# nuc972_core.net
KiCad netlist of a schematic drawn in Altium Designer
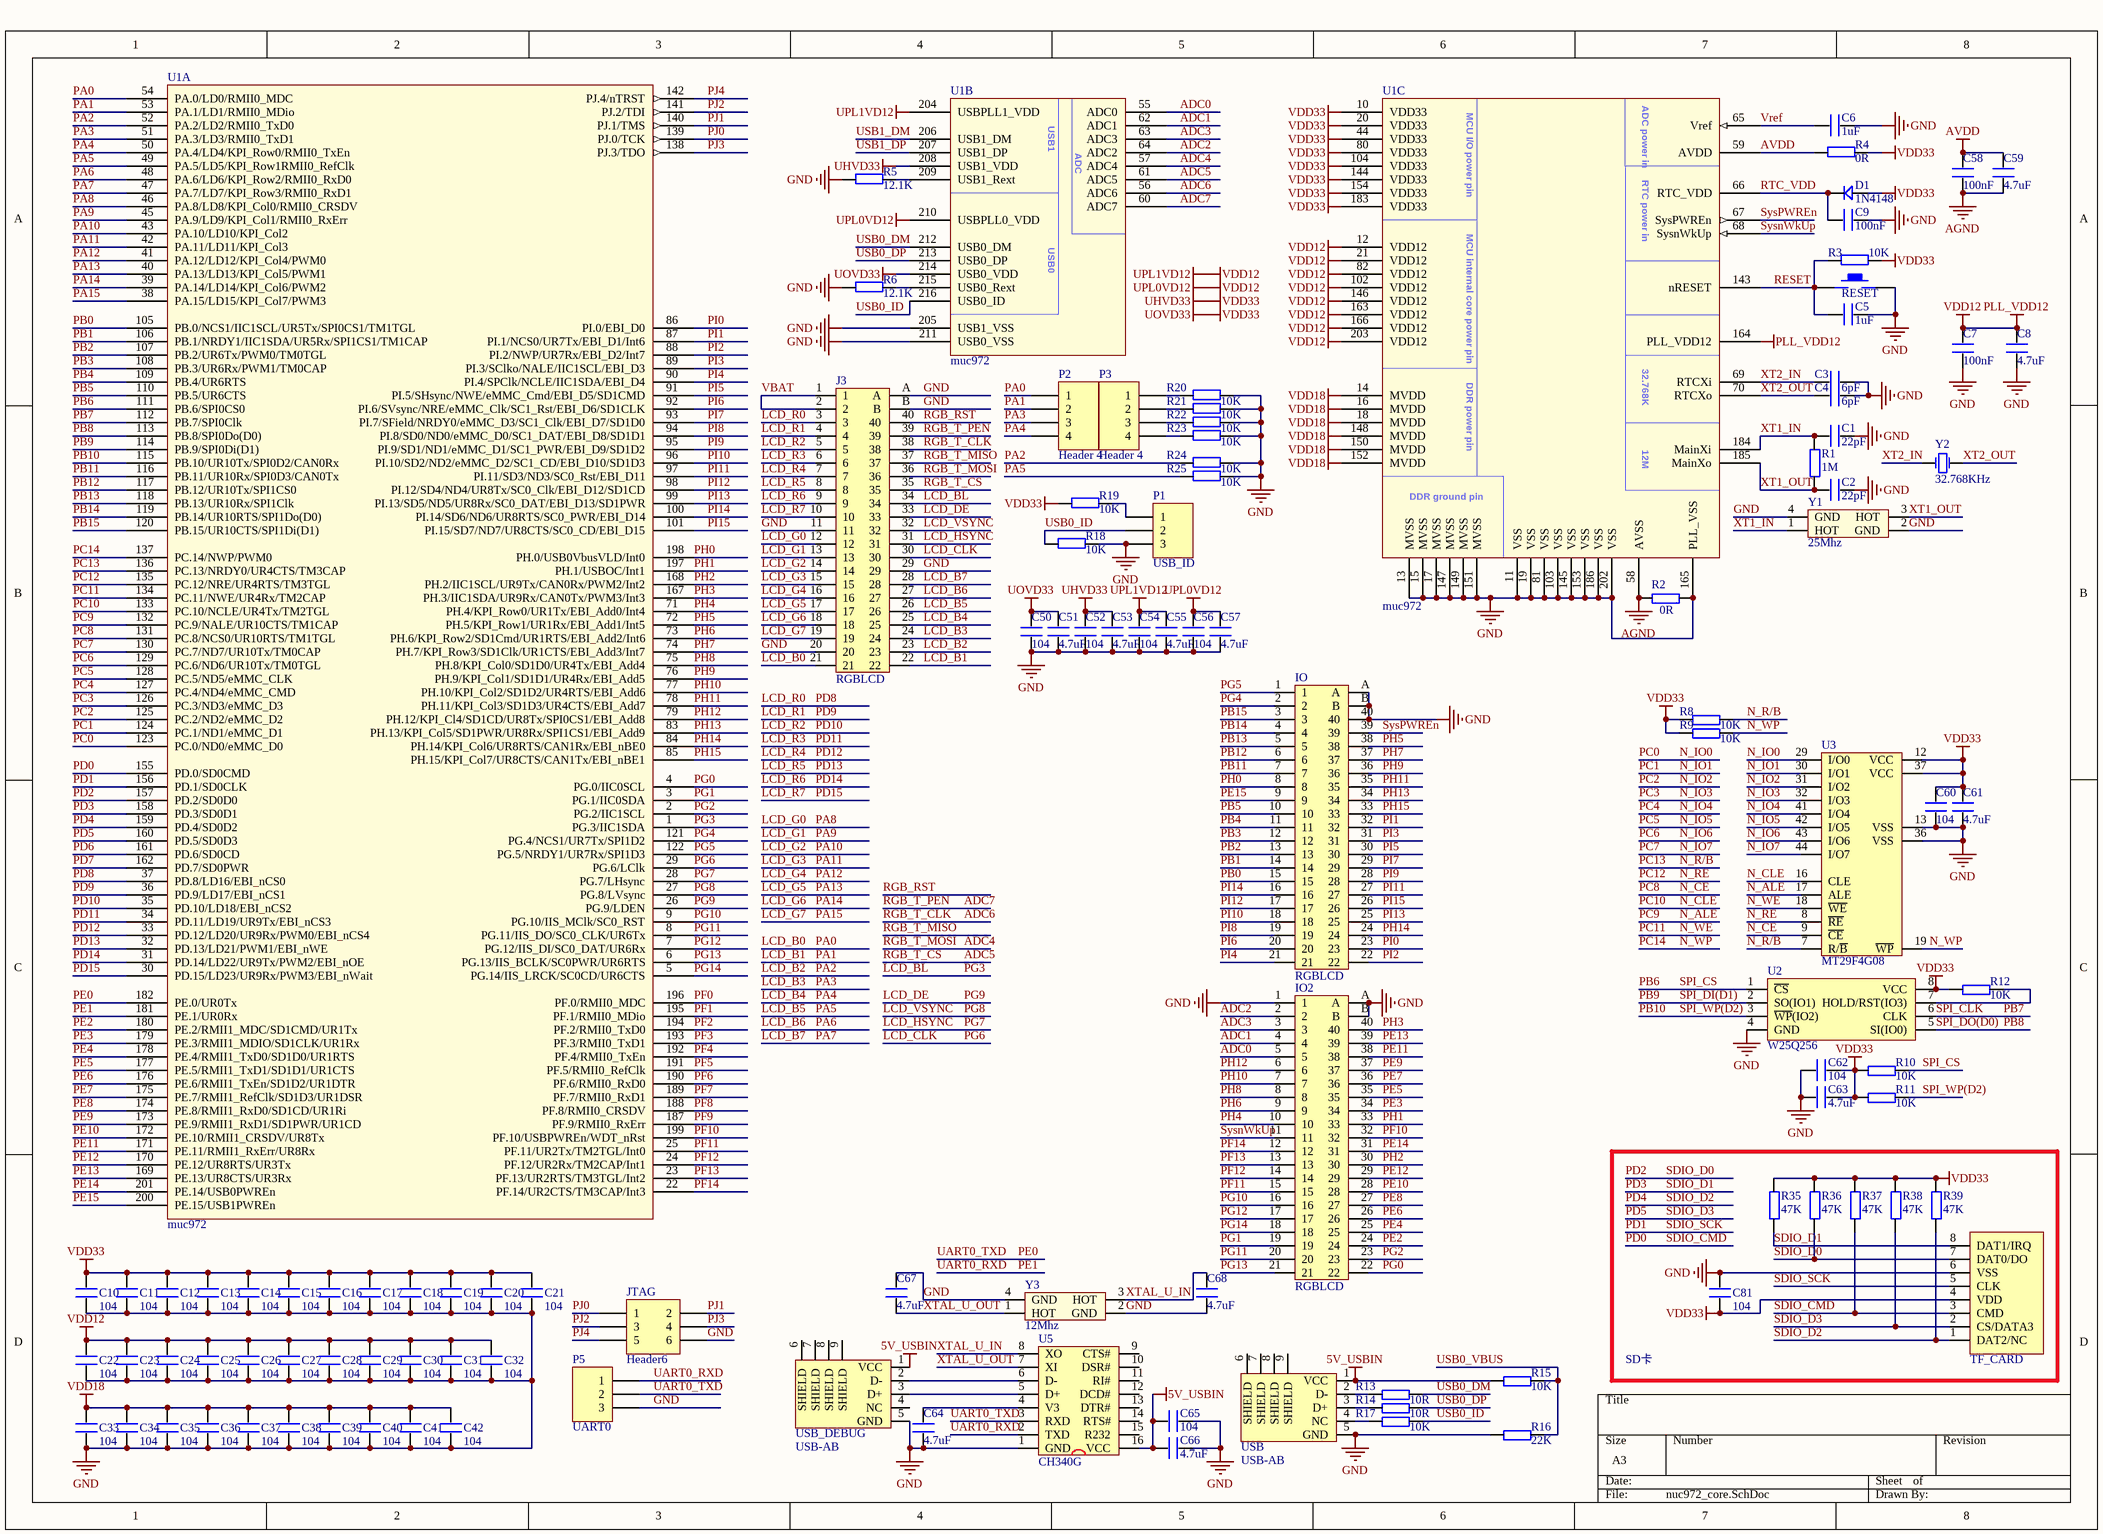
[diagram p0: nuc972_core.SchDoc]

(export (version "E")
  (design (tool "Eeschema 10.0.6"))
  (components
    (comp (ref "C1") (value "22pF") (footprint "C 0603_L") (libsource (lib "阿波罗STM32F4&F7底板封装库") (part "C")))
    (comp (ref "C2") (value "22pF") (footprint "C 0603_L") (libsource (lib "阿波罗STM32F4&F7底板封装库") (part "C")))
    (comp (ref "C3") (value "6pF") (footprint "C 0603_L") (libsource (lib "阿波罗STM32F4&F7底板封装库") (part "C")))
    (comp (ref "C4") (value "6pF") (footprint "C 0603_L") (libsource (lib "阿波罗STM32F4&F7底板封装库") (part "C")))
    (comp (ref "C5") (value "1uF") (footprint "C 0603_L") (libsource (lib "阿波罗STM32F4&F7底板封装库") (part "C")))
    (comp (ref "C6") (value "1uF") (footprint "C 0603_L") (libsource (lib "阿波罗STM32F4&F7底板封装库") (part "C")))
    (comp (ref "C7") (value "100nF") (footprint "C 0603_L") (libsource (lib "阿波罗STM32F4&F7底板封装库") (part "C")))
    (comp (ref "C8") (value "4.7uF") (footprint "C 0603_L") (libsource (lib "阿波罗STM32F4&F7底板封装库") (part "C")))
    (comp (ref "C9") (value "100nF") (footprint "C 0603_L") (libsource (lib "阿波罗STM32F4&F7底板封装库") (part "C")))
    (comp (ref "C10")
      (value "104")
      (footprint "C 0603_L")
      (libsource (lib "阿波罗STM32F4&F7&H7底板封装库") (part "C"))
    )
    (comp (ref "C11")
      (value "104")
      (footprint "C 0603_L")
      (libsource (lib "阿波罗STM32F4&F7&H7底板封装库") (part "C"))
    )
    (comp (ref "C12")
      (value "104")
      (footprint "C 0603_L")
      (libsource (lib "阿波罗STM32F4&F7&H7底板封装库") (part "C"))
    )
    (comp (ref "C13")
      (value "104")
      (footprint "C 0603_L")
      (libsource (lib "阿波罗STM32F4&F7&H7底板封装库") (part "C"))
    )
    (comp (ref "C14")
      (value "104")
      (footprint "C 0603_L")
      (libsource (lib "阿波罗STM32F4&F7&H7底板封装库") (part "C"))
    )
    (comp (ref "C15")
      (value "104")
      (footprint "C 0603_L")
      (libsource (lib "阿波罗STM32F4&F7&H7底板封装库") (part "C"))
    )
    (comp (ref "C16")
      (value "104")
      (footprint "C 0603_L")
      (libsource (lib "阿波罗STM32F4&F7&H7底板封装库") (part "C"))
    )
    (comp (ref "C17")
      (value "104")
      (footprint "C 0603_L")
      (libsource (lib "阿波罗STM32F4&F7&H7底板封装库") (part "C"))
    )
    (comp (ref "C18")
      (value "104")
      (footprint "C 0603_L")
      (libsource (lib "阿波罗STM32F4&F7&H7底板封装库") (part "C"))
    )
    (comp (ref "C19")
      (value "104")
      (footprint "C 0603_L")
      (libsource (lib "阿波罗STM32F4&F7&H7底板封装库") (part "C"))
    )
    (comp (ref "C20")
      (value "104")
      (footprint "C 0603_L")
      (libsource (lib "阿波罗STM32F4&F7&H7底板封装库") (part "C"))
    )
    (comp (ref "C21")
      (value "104")
      (footprint "C 0603_L")
      (libsource (lib "阿波罗STM32F4&F7&H7底板封装库") (part "C"))
    )
    (comp (ref "C22")
      (value "104")
      (footprint "C 0603_L")
      (libsource (lib "阿波罗STM32F4&F7&H7底板封装库") (part "C"))
    )
    (comp (ref "C23")
      (value "104")
      (footprint "C 0603_L")
      (libsource (lib "阿波罗STM32F4&F7&H7底板封装库") (part "C"))
    )
    (comp (ref "C24")
      (value "104")
      (footprint "C 0603_L")
      (libsource (lib "阿波罗STM32F4&F7&H7底板封装库") (part "C"))
    )
    (comp (ref "C25")
      (value "104")
      (footprint "C 0603_L")
      (libsource (lib "阿波罗STM32F4&F7&H7底板封装库") (part "C"))
    )
    (comp (ref "C26")
      (value "104")
      (footprint "C 0603_L")
      (libsource (lib "阿波罗STM32F4&F7&H7底板封装库") (part "C"))
    )
    (comp (ref "C27")
      (value "104")
      (footprint "C 0603_L")
      (libsource (lib "阿波罗STM32F4&F7&H7底板封装库") (part "C"))
    )
    (comp (ref "C28")
      (value "104")
      (footprint "C 0603_L")
      (libsource (lib "阿波罗STM32F4&F7&H7底板封装库") (part "C"))
    )
    (comp (ref "C29")
      (value "104")
      (footprint "C 0603_L")
      (libsource (lib "阿波罗STM32F4&F7&H7底板封装库") (part "C"))
    )
    (comp (ref "C30")
      (value "104")
      (footprint "C 0603_L")
      (libsource (lib "阿波罗STM32F4&F7&H7底板封装库") (part "C"))
    )
    (comp (ref "C31")
      (value "104")
      (footprint "C 0603_L")
      (libsource (lib "阿波罗STM32F4&F7&H7底板封装库") (part "C"))
    )
    (comp (ref "C32")
      (value "104")
      (footprint "C 0603_L")
      (libsource (lib "阿波罗STM32F4&F7&H7底板封装库") (part "C"))
    )
    (comp (ref "C33")
      (value "104")
      (footprint "C 0603_L")
      (libsource (lib "阿波罗STM32F4&F7&H7底板封装库") (part "C"))
    )
    (comp (ref "C34")
      (value "104")
      (footprint "C 0603_L")
      (libsource (lib "阿波罗STM32F4&F7&H7底板封装库") (part "C"))
    )
    (comp (ref "C35")
      (value "104")
      (footprint "C 0603_L")
      (libsource (lib "阿波罗STM32F4&F7&H7底板封装库") (part "C"))
    )
    (comp (ref "C36")
      (value "104")
      (footprint "C 0603_L")
      (libsource (lib "阿波罗STM32F4&F7&H7底板封装库") (part "C"))
    )
    (comp (ref "C37")
      (value "104")
      (footprint "C 0603_L")
      (libsource (lib "阿波罗STM32F4&F7&H7底板封装库") (part "C"))
    )
    (comp (ref "C38")
      (value "104")
      (footprint "C 0603_L")
      (libsource (lib "阿波罗STM32F4&F7&H7底板封装库") (part "C"))
    )
    (comp (ref "C39")
      (value "104")
      (footprint "C 0603_L")
      (libsource (lib "阿波罗STM32F4&F7&H7底板封装库") (part "C"))
    )
    (comp (ref "C40")
      (value "104")
      (footprint "C 0603_L")
      (libsource (lib "阿波罗STM32F4&F7&H7底板封装库") (part "C"))
    )
    (comp (ref "C41")
      (value "104")
      (footprint "C 0603_L")
      (libsource (lib "阿波罗STM32F4&F7&H7底板封装库") (part "C"))
    )
    (comp (ref "C42")
      (value "104")
      (footprint "C 0603_L")
      (libsource (lib "阿波罗STM32F4&F7&H7底板封装库") (part "C"))
    )
    (comp (ref "C50")
      (value "104")
      (footprint "C 0603_L")
      (libsource (lib "阿波罗STM32F4&F7&H7底板封装库") (part "C"))
    )
    (comp (ref "C51")
      (value "4.7uF")
      (footprint "C 0603_L")
      (libsource (lib "阿波罗STM32F4&F7&H7底板封装库") (part "C"))
    )
    (comp (ref "C52")
      (value "104")
      (footprint "C 0603_L")
      (libsource (lib "阿波罗STM32F4&F7&H7底板封装库") (part "C"))
    )
    (comp (ref "C53")
      (value "4.7uF")
      (footprint "C 0603_L")
      (libsource (lib "阿波罗STM32F4&F7&H7底板封装库") (part "C"))
    )
    (comp (ref "C54")
      (value "104")
      (footprint "C 0603_L")
      (libsource (lib "阿波罗STM32F4&F7&H7底板封装库") (part "C"))
    )
    (comp (ref "C55")
      (value "4.7uF")
      (footprint "C 0603_L")
      (libsource (lib "阿波罗STM32F4&F7&H7底板封装库") (part "C"))
    )
    (comp (ref "C56")
      (value "104")
      (footprint "C 0603_L")
      (libsource (lib "阿波罗STM32F4&F7&H7底板封装库") (part "C"))
    )
    (comp (ref "C57")
      (value "4.7uF")
      (footprint "C 0603_L")
      (libsource (lib "阿波罗STM32F4&F7&H7底板封装库") (part "C"))
    )
    (comp (ref "C58")
      (value "100nF")
      (footprint "C 0603_L")
      (libsource (lib "阿波罗STM32F4&F7底板封装库") (part "C"))
    )
    (comp (ref "C59")
      (value "4.7uF")
      (footprint "C 0603_L")
      (libsource (lib "阿波罗STM32F4&F7底板封装库") (part "C"))
    )
    (comp (ref "C60")
      (value "104")
      (footprint "C 0603_L")
      (libsource (lib "阿波罗STM32F4&F7&H7底板封装库") (part "C"))
    )
    (comp (ref "C61")
      (value "4.7uF")
      (footprint "C 0603_L")
      (libsource (lib "阿波罗STM32F4&F7&H7底板封装库") (part "C"))
    )
    (comp (ref "C62")
      (value "104")
      (footprint "C 0603_L")
      (libsource (lib "阿波罗STM32F4&F7&H7底板封装库") (part "C"))
    )
    (comp (ref "C63")
      (value "4.7uF")
      (footprint "C 0603_L")
      (libsource (lib "阿波罗STM32F4&F7&H7底板封装库") (part "C"))
    )
    (comp (ref "C64")
      (value "4.7uF")
      (footprint "C 0603_L")
      (libsource (lib "阿波罗STM32F4&F7&H7底板封装库") (part "C"))
    )
    (comp (ref "C65")
      (value "104")
      (footprint "C 0603_L")
      (libsource (lib "阿波罗STM32F4&F7&H7底板封装库") (part "C"))
    )
    (comp (ref "C66")
      (value "4.7uF")
      (footprint "C 0603_L")
      (libsource (lib "阿波罗STM32F4&F7&H7底板封装库") (part "C"))
    )
    (comp (ref "C67")
      (value "4.7uF")
      (footprint "C 0603_L")
      (libsource (lib "阿波罗STM32F4&F7&H7底板封装库") (part "C"))
    )
    (comp (ref "C68")
      (value "4.7uF")
      (footprint "C 0603_L")
      (libsource (lib "阿波罗STM32F4&F7&H7底板封装库") (part "C"))
    )
    (comp (ref "C81")
      (value "104")
      (footprint "C 0603_L")
      (libsource (lib "阿波罗STM32F4&F7&H7底板封装库") (part "C"))
    )
    (comp (ref "D1")
      (value "1N4148")
      (footprint "MINI_MELF (LL34)")
      (libsource (lib "阿波罗STM32F4&F7&H7底板封装库") (part "D"))
    )
    (comp (ref "IO")
      (value "RGBLCD")
      (footprint "FPC-TOP40")
      (description "FPC-40P-0.5mm")
      (libsource (lib "STM32F429核心板封装库") (part "FPC-40"))
    )
    (comp (ref "IO2")
      (value "RGBLCD")
      (footprint "FPC-TOP40")
      (description "FPC-40P-0.5mm")
      (libsource (lib "STM32F429核心板封装库") (part "FPC-40"))
    )
    (comp (ref "J3")
      (value "RGBLCD")
      (footprint "FPC-TOP40")
      (description "FPC-40P-0.5mm")
      (libsource (lib "STM32F429核心板封装库") (part "FPC-40"))
    )
    (comp (ref "JTAG")
      (value "Header6")
      (footprint "HDR2.54-LI-6P")
      (description "Header, 3-Pin, Dual row")
      (fields (field (name "PUBLISHER") "Altium Limited"))
      (libsource (lib "阿波罗STM32F4&F7底板封装库") (part "Header 3X2"))
    )
    (comp (ref "P1")
      (value "USB_ID")
      (footprint "HDR2.54-LI-3P")
      (description "Header, 3-Pin")
      (fields (field (name "PUBLISHER") "Altium Limited"))
      (libsource (lib "") (part "Header 3_1"))
    )
    (comp (ref "P2")
      (value "Header 4")
      (footprint "HDR2.54-LI-4P")
      (description "Header, 4-Pin")
      (fields (field (name "PUBLISHER") "Altium Limited"))
      (libsource (lib "阿波罗STM32F4&F7底板封装库") (part "Header 4"))
    )
    (comp (ref "P3")
      (value "Header 4")
      (footprint "HDR2.54-LI-4P")
      (description "Header, 4-Pin")
      (fields (field (name "PUBLISHER") "Altium Limited"))
      (libsource (lib "") (part "Header 4_1"))
    )
    (comp (ref "P5")
      (value "UART0")
      (footprint "HDR2.54-LI-3P")
      (description "Header, 3-Pin")
      (fields (field (name "PUBLISHER") "Altium Limited"))
      (libsource (lib "STM32H743核心板封装库") (part "Header 3"))
    )
    (comp (ref "R1") (value "1M") (footprint "R 0603_L") (libsource (lib "阿波罗STM32F4&F7底板封装库") (part "R")))
    (comp (ref "R2") (value "0R") (footprint "R 0603_L") (libsource (lib "阿波罗STM32F4&F7底板封装库") (part "R")))
    (comp (ref "R3") (value "10K") (footprint "R 0603_L") (libsource (lib "阿波罗STM32F4&F7底板封装库") (part "R")))
    (comp (ref "R4") (value "0R") (footprint "R 0603_L") (libsource (lib "阿波罗STM32F4&F7底板封装库") (part "R")))
    (comp (ref "R5") (value "12.1K") (footprint "R 0603_L") (libsource (lib "阿波罗STM32F4&F7底板封装库") (part "R")))
    (comp (ref "R6") (value "12.1K") (footprint "R 0603_L") (libsource (lib "阿波罗STM32F4&F7底板封装库") (part "R")))
    (comp (ref "R8") (value "10K") (footprint "R 0603_L") (libsource (lib "阿波罗STM32F4&F7底板封装库") (part "R")))
    (comp (ref "R9") (value "10K") (footprint "R 0603_L") (libsource (lib "阿波罗STM32F4&F7底板封装库") (part "R")))
    (comp (ref "R10") (value "10K") (footprint "R 0603_L") (libsource (lib "阿波罗STM32F4&F7底板封装库") (part "R")))
    (comp (ref "R11") (value "10K") (footprint "R 0603_L") (libsource (lib "阿波罗STM32F4&F7底板封装库") (part "R")))
    (comp (ref "R12") (value "10K") (footprint "R 0603_L") (libsource (lib "阿波罗STM32F4&F7底板封装库") (part "R")))
    (comp (ref "R13") (value "10R") (footprint "R 0603_L") (libsource (lib "阿波罗STM32F4&F7底板封装库") (part "R")))
    (comp (ref "R14") (value "10R") (footprint "R 0603_L") (libsource (lib "阿波罗STM32F4&F7底板封装库") (part "R")))
    (comp (ref "R15") (value "10K") (footprint "R 0603_L") (libsource (lib "阿波罗STM32F4&F7底板封装库") (part "R")))
    (comp (ref "R16") (value "22K") (footprint "R 0603_L") (libsource (lib "阿波罗STM32F4&F7底板封装库") (part "R")))
    (comp (ref "R17") (value "10K") (footprint "R 0603_L") (libsource (lib "阿波罗STM32F4&F7底板封装库") (part "R")))
    (comp (ref "R18") (value "10K") (footprint "R 0603_L") (libsource (lib "阿波罗STM32F4&F7底板封装库") (part "R")))
    (comp (ref "R19") (value "10K") (footprint "R 0603_L") (libsource (lib "阿波罗STM32F4&F7底板封装库") (part "R")))
    (comp (ref "R20") (value "10K") (footprint "R 0603_L") (libsource (lib "阿波罗STM32F4&F7底板封装库") (part "R")))
    (comp (ref "R21") (value "10K") (footprint "R 0603_L") (libsource (lib "阿波罗STM32F4&F7底板封装库") (part "R")))
    (comp (ref "R22") (value "10K") (footprint "R 0603_L") (libsource (lib "阿波罗STM32F4&F7底板封装库") (part "R")))
    (comp (ref "R23") (value "10K") (footprint "R 0603_L") (libsource (lib "阿波罗STM32F4&F7底板封装库") (part "R")))
    (comp (ref "R24") (value "10K") (footprint "R 0603_L") (libsource (lib "阿波罗STM32F4&F7底板封装库") (part "R")))
    (comp (ref "R25") (value "10K") (footprint "R 0603_L") (libsource (lib "阿波罗STM32F4&F7底板封装库") (part "R")))
    (comp (ref "R35") (value "47K") (footprint "R 0603_L") (libsource (lib "阿波罗STM32F4&F7底板封装库") (part "R")))
    (comp (ref "R36") (value "47K") (footprint "R 0603_L") (libsource (lib "阿波罗STM32F4&F7底板封装库") (part "R")))
    (comp (ref "R37") (value "47K") (footprint "R 0603_L") (libsource (lib "阿波罗STM32F4&F7底板封装库") (part "R")))
    (comp (ref "R38") (value "47K") (footprint "R 0603_L") (libsource (lib "阿波罗STM32F4&F7底板封装库") (part "R")))
    (comp (ref "R39") (value "47K") (footprint "R 0603_L") (libsource (lib "阿波罗STM32F4&F7底板封装库") (part "R")))
    (comp (ref "RESET")
      (value "KEY_M")
      (footprint "TSW DIP-6*6*5")
      (libsource (lib "阿波罗STM32F4&F7&H7底板封装库") (part "KEY_M"))
    )
    (comp (ref "TF_CARD")
      (value "SD-MICRO-TF")
      (footprint "SD-MICRO-TF")
      (description "SD,MICRO,TF")
      (libsource (lib "Pandora_STM32L4_Board_V2.4") (part "SD-MICRO-TF"))
    )
    (comp (ref "U1") (value "muc972") (footprint "LQFP_216") (libsource (lib "nuc972lib") (part "LQFP_216")))
    (comp (ref "U2")
      (value "W25Q256")
      (footprint "SOP8W_N")
      (description "W25Q128")
      (libsource (lib "STM32H743核心板封装库") (part "W25Q128"))
    )
    (comp (ref "U3")
      (value "MT29F4G08")
      (footprint "TSOP48")
      (description "256MB NAND FLASH")
      (libsource (lib "STM32H743核心板封装库") (part "K9F2G08U0C"))
    )
    (comp (ref "U5")
      (value "CH340G")
      (footprint "SOP16_N")
      (description "USB2UART")
      (libsource (lib "阿波罗STM32F4&F7底板封装库") (part "CH340G"))
    )
    (comp (ref "USB")
      (value "USB-AB")
      (footprint "USB-MICRO_B")
      (description "MicroUSB")
      (libsource (lib "STM32H743核心板封装库") (part "USB-AB"))
    )
    (comp (ref "USB_DEBUG")
      (value "USB-AB")
      (footprint "USB-MICRO_B")
      (description "MicroUSB")
      (libsource (lib "STM32H743核心板封装库") (part "USB-AB"))
    )
    (comp (ref "Y1")
      (value "25Mhz")
      (footprint "OSC 3225-4P")
      (description "3225贴片无源晶振")
      (libsource (lib "STM32H743核心板封装库") (part "XTAL_3225"))
    )
    (comp (ref "Y2")
      (value "32.768KHz")
      (footprint "OSC 3215-2P")
      (description "普通晶振")
      (fields (field (name "PUBLISHER") "Altium Limited"))
      (libsource (lib "STM32H743核心板封装库") (part "XTAL"))
    )
    (comp (ref "Y3")
      (value "12Mhz")
      (footprint "OSC 3225-4P")
      (description "3225贴片无源晶振")
      (libsource (lib "STM32H743核心板封装库") (part "XTAL_3225"))
    )
  )
  (nets
    (net (code "1") (name "/ADC0") (class "Default")
      (node (ref "IO2") (pin "5") (pinfunction "5_5") (pintype "passive"))
      (node (ref "U1") (pin "55") (pinfunction "ADC0_55") (pintype "passive"))
    )
    (net (code "2") (name "/ADC1") (class "Default")
      (node (ref "IO2") (pin "4") (pinfunction "4_4") (pintype "passive"))
      (node (ref "U1") (pin "62") (pinfunction "ADC1_62") (pintype "passive"))
    )
    (net (code "3") (name "/ADC2") (class "Default")
      (node (ref "IO2") (pin "2") (pinfunction "2_2") (pintype "passive"))
      (node (ref "U1") (pin "64") (pinfunction "ADC2_64") (pintype "passive"))
    )
    (net (code "4") (name "/ADC3") (class "Default")
      (node (ref "IO2") (pin "3") (pinfunction "3_3") (pintype "passive"))
      (node (ref "U1") (pin "63") (pinfunction "ADC3_63") (pintype "passive"))
    )
    (net (code "5") (name "/ADC4") (class "Default")
      (node (ref "J3") (pin "36") (pinfunction "36_36") (pintype "passive"))
      (node (ref "U1") (pin "57") (pinfunction "ADC4_57") (pintype "passive"))
    )
    (net (code "6") (name "/ADC5") (class "Default")
      (node (ref "J3") (pin "35") (pinfunction "35_35") (pintype "passive"))
      (node (ref "U1") (pin "61") (pinfunction "ADC5_61") (pintype "passive"))
    )
    (net (code "7") (name "/ADC6") (class "Default")
      (node (ref "J3") (pin "38") (pinfunction "38_38") (pintype "passive"))
      (node (ref "U1") (pin "56") (pinfunction "ADC6_56") (pintype "passive"))
    )
    (net (code "8") (name "/ADC7") (class "Default")
      (node (ref "J3") (pin "39") (pinfunction "39_39") (pintype "passive"))
      (node (ref "U1") (pin "60") (pinfunction "ADC7_60") (pintype "passive"))
    )
    (net (code "9") (name "/LCD_B0") (class "Default")
      (node (ref "J3") (pin "21") (pinfunction "21_21") (pintype "passive"))
      (node (ref "P2") (pin "1") (pinfunction "1_1") (pintype "passive"))
      (node (ref "U1") (pin "54") (pinfunction "PA.0/LD0/RMII0_MDC_54") (pintype "passive"))
    )
    (net (code "10") (name "/LCD_B1") (class "Default")
      (node (ref "J3") (pin "22") (pinfunction "22_22") (pintype "passive"))
      (node (ref "P2") (pin "2") (pinfunction "2_2") (pintype "passive"))
      (node (ref "U1") (pin "53") (pinfunction "PA.1/LD1/RMII0_MDio_53") (pintype "passive"))
    )
    (net (code "11") (name "/LCD_B2") (class "Default")
      (node (ref "J3") (pin "23") (pinfunction "23_23") (pintype "passive"))
      (node (ref "R24") (pin "2") (pintype "passive"))
      (node (ref "U1") (pin "52") (pinfunction "PA.2/LD2/RMII0_TxD0_52") (pintype "passive"))
    )
    (net (code "12") (name "/LCD_B3") (class "Default")
      (node (ref "J3") (pin "24") (pinfunction "24_24") (pintype "passive"))
      (node (ref "P2") (pin "3") (pinfunction "3_3") (pintype "passive"))
      (node (ref "U1") (pin "51") (pinfunction "PA.3/LD3/RMII0_TxD1_51") (pintype "passive"))
    )
    (net (code "13") (name "/LCD_B4") (class "Default")
      (node (ref "J3") (pin "25") (pinfunction "25_25") (pintype "passive"))
      (node (ref "P2") (pin "4") (pinfunction "4_4") (pintype "passive"))
      (node (ref "U1") (pin "50") (pinfunction "PA.4/LD4/KPI_Row0/RMII0_TxEn_50") (pintype "passive"))
    )
    (net (code "14") (name "/LCD_B5") (class "Default")
      (node (ref "J3") (pin "26") (pinfunction "26_26") (pintype "passive"))
      (node (ref "R25") (pin "2") (pintype "passive"))
      (node (ref "U1") (pin "49") (pinfunction "PA.5/LD5/KPI_Row1RMII0_RefClk_49") (pintype "passive"))
    )
    (net (code "15") (name "/LCD_B6") (class "Default")
      (node (ref "J3") (pin "27") (pinfunction "27_27") (pintype "passive"))
      (node (ref "U1") (pin "48") (pinfunction "PA.6/LD6/KPI_Row2/RMII0_RxD0_48") (pintype "passive"))
    )
    (net (code "16") (name "/LCD_B7") (class "Default")
      (node (ref "J3") (pin "28") (pinfunction "28_28") (pintype "passive"))
      (node (ref "U1") (pin "47") (pinfunction "PA.7/LD7/KPI_Row3/RMII0_RxD1_47") (pintype "passive"))
    )
    (net (code "17") (name "/LCD_BL") (class "Default")
      (node (ref "J3") (pin "34") (pinfunction "34_34") (pintype "passive"))
      (node (ref "U1") (pin "1") (pinfunction "PG.3/IIC1SDA_1") (pintype "passive"))
    )
    (net (code "18") (name "/LCD_CLK") (class "Default")
      (node (ref "J3") (pin "30") (pinfunction "30_30") (pintype "passive"))
      (node (ref "U1") (pin "29") (pinfunction "PG.6/LClk_29") (pintype "passive"))
    )
    (net (code "19") (name "/LCD_DE") (class "Default")
      (node (ref "J3") (pin "33") (pinfunction "33_33") (pintype "passive"))
      (node (ref "U1") (pin "26") (pinfunction "PG.9/LDEN_26") (pintype "passive"))
    )
    (net (code "20") (name "/LCD_G0") (class "Default")
      (node (ref "J3") (pin "12") (pinfunction "12_12") (pintype "passive"))
      (node (ref "U1") (pin "46") (pinfunction "PA.8/LD8/KPI_Col0/RMII0_CRSDV_46") (pintype "passive"))
    )
    (net (code "21") (name "/LCD_G1") (class "Default")
      (node (ref "J3") (pin "13") (pinfunction "13_13") (pintype "passive"))
      (node (ref "U1") (pin "45") (pinfunction "PA.9/LD9/KPI_Col1/RMII0_RxErr_45") (pintype "passive"))
    )
    (net (code "22") (name "/LCD_G2") (class "Default")
      (node (ref "J3") (pin "14") (pinfunction "14_14") (pintype "passive"))
      (node (ref "U1") (pin "43") (pinfunction "PA.10/LD10/KPI_Col2_43") (pintype "passive"))
    )
    (net (code "23") (name "/LCD_G3") (class "Default")
      (node (ref "J3") (pin "15") (pinfunction "15_15") (pintype "passive"))
      (node (ref "U1") (pin "42") (pinfunction "PA.11/LD11/KPI_Col3_42") (pintype "passive"))
    )
    (net (code "24") (name "/LCD_G4") (class "Default")
      (node (ref "J3") (pin "16") (pinfunction "16_16") (pintype "passive"))
      (node (ref "U1") (pin "41") (pinfunction "PA.12/LD12/KPI_Col4/PWM0_41") (pintype "passive"))
    )
    (net (code "25") (name "/LCD_G5") (class "Default")
      (node (ref "J3") (pin "17") (pinfunction "17_17") (pintype "passive"))
      (node (ref "U1") (pin "40") (pinfunction "PA.13/LD13/KPI_Col5/PWM1_40") (pintype "passive"))
    )
    (net (code "26") (name "/LCD_G6") (class "Default")
      (node (ref "J3") (pin "18") (pinfunction "18_18") (pintype "passive"))
      (node (ref "U1") (pin "39") (pinfunction "PA.14/LD14/KPI_Col6/PWM2_39") (pintype "passive"))
    )
    (net (code "27") (name "/LCD_G7") (class "Default")
      (node (ref "J3") (pin "19") (pinfunction "19_19") (pintype "passive"))
      (node (ref "U1") (pin "38") (pinfunction "PA.15/LD15/KPI_Col7/PWM3_38") (pintype "passive"))
    )
    (net (code "28") (name "/LCD_HSYNC") (class "Default")
      (node (ref "J3") (pin "31") (pinfunction "31_31") (pintype "passive"))
      (node (ref "U1") (pin "28") (pinfunction "PG.7/LHsync_28") (pintype "passive"))
    )
    (net (code "29") (name "/LCD_R0") (class "Default")
      (node (ref "J3") (pin "3") (pinfunction "3_3") (pintype "passive"))
      (node (ref "U1") (pin "37") (pinfunction "PD.8/LD16/EBI_nCS0_37") (pintype "passive"))
    )
    (net (code "30") (name "/LCD_R1") (class "Default")
      (node (ref "J3") (pin "4") (pinfunction "4_4") (pintype "passive"))
      (node (ref "U1") (pin "36") (pinfunction "PD.9/LD17/EBI_nCS1_36") (pintype "passive"))
    )
    (net (code "31") (name "/LCD_R2") (class "Default")
      (node (ref "J3") (pin "5") (pinfunction "5_5") (pintype "passive"))
      (node (ref "U1") (pin "35") (pinfunction "PD.10/LD18/EBI_nCS2_35") (pintype "passive"))
    )
    (net (code "32") (name "/LCD_R3") (class "Default")
      (node (ref "J3") (pin "6") (pinfunction "6_6") (pintype "passive"))
      (node (ref "U1") (pin "34") (pinfunction "PD.11/LD19/UR9Tx/EBI_nCS3_34") (pintype "passive"))
    )
    (net (code "33") (name "/LCD_R4") (class "Default")
      (node (ref "J3") (pin "7") (pinfunction "7_7") (pintype "passive"))
      (node (ref "U1") (pin "33") (pinfunction "PD.12/LD20/UR9Rx/PWM0/EBI_nCS4_33") (pintype "passive"))
    )
    (net (code "34") (name "/LCD_R5") (class "Default")
      (node (ref "J3") (pin "8") (pinfunction "8_8") (pintype "passive"))
      (node (ref "U1") (pin "32") (pinfunction "PD.13/LD21/PWM1/EBI_nWE_32") (pintype "passive"))
    )
    (net (code "35") (name "/LCD_R6") (class "Default")
      (node (ref "J3") (pin "9") (pinfunction "9_9") (pintype "passive"))
      (node (ref "U1") (pin "31") (pinfunction "PD.14/LD22/UR9Tx/PWM2/EBI_nOE_31") (pintype "passive"))
    )
    (net (code "36") (name "/LCD_R7") (class "Default")
      (node (ref "J3") (pin "10") (pinfunction "10_10") (pintype "passive"))
      (node (ref "U1") (pin "30") (pinfunction "PD.15/LD23/UR9Rx/PWM3/EBI_nWait_30") (pintype "passive"))
    )
    (net (code "37") (name "/LCD_VSYNC") (class "Default")
      (node (ref "J3") (pin "32") (pinfunction "32_32") (pintype "passive"))
      (node (ref "U1") (pin "27") (pinfunction "PG.8/LVsync_27") (pintype "passive"))
    )
    (net (code "38") (name "/N_ALE") (class "Default")
      (node (ref "U1") (pin "132") (pinfunction "PC.9/NALE/UR10CTS/TM1CAP_132") (pintype "passive"))
      (node (ref "U3") (pin "17") (pinfunction "ALE_17") (pintype "passive"))
    )
    (net (code "39") (name "/N_CE") (class "Default")
      (node (ref "U1") (pin "131") (pinfunction "PC.8/NCS0/UR10RTS/TM1TGL_131") (pintype "passive"))
      (node (ref "U3") (pin "9") (pinfunction "~{CE}_9") (pintype "passive"))
    )
    (net (code "40") (name "/N_CLE") (class "Default")
      (node (ref "U1") (pin "133") (pinfunction "PC.10/NCLE/UR4Tx/TM2TGL_133") (pintype "passive"))
      (node (ref "U3") (pin "16") (pinfunction "CLE_16") (pintype "passive"))
    )
    (net (code "41") (name "/N_IO0") (class "Default")
      (node (ref "U1") (pin "123") (pinfunction "PC.0/ND0/eMMC_D0_123") (pintype "passive"))
      (node (ref "U3") (pin "29") (pinfunction "I/O0_29") (pintype "passive"))
    )
    (net (code "42") (name "/N_IO1") (class "Default")
      (node (ref "U1") (pin "124") (pinfunction "PC.1/ND1/eMMC_D1_124") (pintype "passive"))
      (node (ref "U3") (pin "30") (pinfunction "I/O1_30") (pintype "passive"))
    )
    (net (code "43") (name "/N_IO2") (class "Default")
      (node (ref "U1") (pin "125") (pinfunction "PC.2/ND2/eMMC_D2_125") (pintype "passive"))
      (node (ref "U3") (pin "31") (pinfunction "I/O2_31") (pintype "passive"))
    )
    (net (code "44") (name "/N_IO3") (class "Default")
      (node (ref "U1") (pin "126") (pinfunction "PC.3/ND3/eMMC_D3_126") (pintype "passive"))
      (node (ref "U3") (pin "32") (pinfunction "I/O3_32") (pintype "passive"))
    )
    (net (code "45") (name "/N_IO4") (class "Default")
      (node (ref "U1") (pin "127") (pinfunction "PC.4/ND4/eMMC_CMD_127") (pintype "passive"))
      (node (ref "U3") (pin "41") (pinfunction "I/O4_41") (pintype "passive"))
    )
    (net (code "46") (name "/N_IO5") (class "Default")
      (node (ref "U1") (pin "128") (pinfunction "PC.5/ND5/eMMC_CLK_128") (pintype "passive"))
      (node (ref "U3") (pin "42") (pinfunction "I/O5_42") (pintype "passive"))
    )
    (net (code "47") (name "/N_IO6") (class "Default")
      (node (ref "U1") (pin "129") (pinfunction "PC.6/ND6/UR10Tx/TM0TGL_129") (pintype "passive"))
      (node (ref "U3") (pin "43") (pinfunction "I/O6_43") (pintype "passive"))
    )
    (net (code "48") (name "/N_IO7") (class "Default")
      (node (ref "U1") (pin "130") (pinfunction "PC.7/ND7/UR10Tx/TM0CAP_130") (pintype "passive"))
      (node (ref "U3") (pin "44") (pinfunction "I/O7_44") (pintype "passive"))
    )
    (net (code "49") (name "/N_RE") (class "Default")
      (node (ref "U1") (pin "135") (pinfunction "PC.12/NRE/UR4RTS/TM3TGL_135") (pintype "passive"))
      (node (ref "U3") (pin "8") (pinfunction "~{RE}_8") (pintype "passive"))
    )
    (net (code "50") (name "/N_R{slash}B") (class "Default")
      (node (ref "R8") (pin "2") (pintype "passive"))
      (node (ref "U1") (pin "136") (pinfunction "PC.13/NRDY0/UR4CTS/TM3CAP_136") (pintype "passive"))
      (node (ref "U3") (pin "7") (pinfunction "R/~{B}_7") (pintype "passive"))
    )
    (net (code "51") (name "/N_WE") (class "Default")
      (node (ref "U1") (pin "134") (pinfunction "PC.11/NWE/UR4Rx/TM2CAP_134") (pintype "passive"))
      (node (ref "U3") (pin "18") (pinfunction "~{WE}_18") (pintype "passive"))
    )
    (net (code "52") (name "/N_WP") (class "Default")
      (node (ref "R9") (pin "2") (pintype "passive"))
      (node (ref "U1") (pin "137") (pinfunction "PC.14/NWP/PWM0_137") (pintype "passive"))
      (node (ref "U3") (pin "19") (pinfunction "~{WP}_19") (pintype "passive"))
    )
    (net (code "53") (name "/PB0") (class "Default")
      (node (ref "IO") (pin "15") (pinfunction "15_15") (pintype "passive"))
      (node (ref "U1") (pin "105") (pinfunction "PB.0/NCS1/IIC1SCL/UR5Tx/SPI0CS1/TM1TGL_105") (pintype "passive"))
    )
    (net (code "54") (name "/PB1") (class "Default")
      (node (ref "IO") (pin "14") (pinfunction "14_14") (pintype "passive"))
      (node (ref "U1") (pin "106") (pinfunction "PB.1/NRDY1/IIC1SDA/UR5Rx/SPI1CS1/TM1CAP_106") (pintype "passive"))
    )
    (net (code "55") (name "/PB2") (class "Default")
      (node (ref "IO") (pin "13") (pinfunction "13_13") (pintype "passive"))
      (node (ref "U1") (pin "107") (pinfunction "PB.2/UR6Tx/PWM0/TM0TGL_107") (pintype "passive"))
    )
    (net (code "56") (name "/PB3") (class "Default")
      (node (ref "IO") (pin "12") (pinfunction "12_12") (pintype "passive"))
      (node (ref "U1") (pin "108") (pinfunction "PB.3/UR6Rx/PWM1/TM0CAP_108") (pintype "passive"))
    )
    (net (code "57") (name "/PB4") (class "Default")
      (node (ref "IO") (pin "11") (pinfunction "11_11") (pintype "passive"))
      (node (ref "U1") (pin "109") (pinfunction "PB.4/UR6RTS_109") (pintype "passive"))
    )
    (net (code "58") (name "/PB5") (class "Default")
      (node (ref "IO") (pin "10") (pinfunction "10_10") (pintype "passive"))
      (node (ref "U1") (pin "110") (pinfunction "PB.5/UR6CTS_110") (pintype "passive"))
    )
    (net (code "59") (name "/PB6") (class "Default")
      (node (ref "R10") (pin "2") (pintype "passive"))
      (node (ref "U1") (pin "111") (pinfunction "PB.6/SPI0CS0_111") (pintype "passive"))
      (node (ref "U2") (pin "1") (pinfunction "~{CS}_1") (pintype "passive"))
    )
    (net (code "60") (name "/PB7") (class "Default")
      (node (ref "U1") (pin "112") (pinfunction "PB.7/SPI0Clk_112") (pintype "passive"))
      (node (ref "U2") (pin "6") (pinfunction "CLK_6") (pintype "passive"))
    )
    (net (code "61") (name "/PB8") (class "Default")
      (node (ref "U1") (pin "113") (pinfunction "PB.8/SPI0Do(D0)_113") (pintype "passive"))
      (node (ref "U2") (pin "5") (pinfunction "SI(IO0)_5") (pintype "power_in"))
    )
    (net (code "62") (name "/PB9") (class "Default")
      (node (ref "U1") (pin "114") (pinfunction "PB.9/SPI0Di(D1)_114") (pintype "passive"))
      (node (ref "U2") (pin "2") (pinfunction "SO(IO1)_2") (pintype "passive"))
    )
    (net (code "63") (name "/PB10") (class "Default")
      (node (ref "R11") (pin "2") (pintype "passive"))
      (node (ref "U1") (pin "115") (pinfunction "PB.10/UR10Tx/SPI0D2/CAN0Rx_115") (pintype "passive"))
      (node (ref "U2") (pin "3") (pinfunction "~{WP}(IO2)_3") (pintype "passive"))
    )
    (net (code "64") (name "/PB11") (class "Default")
      (node (ref "IO") (pin "7") (pinfunction "7_7") (pintype "passive"))
      (node (ref "U1") (pin "116") (pinfunction "PB.11/UR10Rx/SPI0D3/CAN0Tx_116") (pintype "passive"))
    )
    (net (code "65") (name "/PB12") (class "Default")
      (node (ref "IO") (pin "6") (pinfunction "6_6") (pintype "passive"))
      (node (ref "U1") (pin "117") (pinfunction "PB.12/UR10Tx/SPI1CS0_117") (pintype "passive"))
    )
    (net (code "66") (name "/PB13") (class "Default")
      (node (ref "IO") (pin "5") (pinfunction "5_5") (pintype "passive"))
      (node (ref "U1") (pin "118") (pinfunction "PB.13/UR10Rx/SPI1Clk_118") (pintype "passive"))
    )
    (net (code "67") (name "/PB14") (class "Default")
      (node (ref "IO") (pin "4") (pinfunction "4_4") (pintype "passive"))
      (node (ref "U1") (pin "119") (pinfunction "PB.14/UR10RTS/SPI1Do(D0)_119") (pintype "passive"))
    )
    (net (code "68") (name "/PB15") (class "Default")
      (node (ref "IO") (pin "3") (pinfunction "3_3") (pintype "passive"))
      (node (ref "U1") (pin "120") (pinfunction "PB.15/UR10CTS/SPI1Di(D1)_120") (pintype "passive"))
    )
    (net (code "69") (name "/PD0") (class "Default")
      (node (ref "R37") (pin "1") (pintype "passive"))
      (node (ref "TF_CARD") (pin "3") (pinfunction "CMD_3") (pintype "passive"))
      (node (ref "U1") (pin "155") (pinfunction "PD.0/SD0CMD_155") (pintype "passive"))
    )
    (net (code "70") (name "/PD1") (class "Default")
      (node (ref "TF_CARD") (pin "5") (pinfunction "CLK_5") (pintype "passive"))
      (node (ref "U1") (pin "156") (pinfunction "PD.1/SD0CLK_156") (pintype "passive"))
    )
    (net (code "71") (name "/PD2") (class "Default")
      (node (ref "R36") (pin "1") (pintype "passive"))
      (node (ref "TF_CARD") (pin "7") (pinfunction "DAT0/DO_7") (pintype "passive"))
      (node (ref "U1") (pin "157") (pinfunction "PD.2/SD0D0_157") (pintype "passive"))
    )
    (net (code "72") (name "/PD3") (class "Default")
      (node (ref "R35") (pin "1") (pintype "passive"))
      (node (ref "TF_CARD") (pin "8") (pinfunction "DAT1/IRQ_8") (pintype "passive"))
      (node (ref "U1") (pin "158") (pinfunction "PD.3/SD0D1_158") (pintype "passive"))
    )
    (net (code "73") (name "/PD4") (class "Default")
      (node (ref "R39") (pin "1") (pintype "passive"))
      (node (ref "TF_CARD") (pin "1") (pinfunction "DAT2/NC_1") (pintype "passive"))
      (node (ref "U1") (pin "159") (pinfunction "PD.4/SD0D2_159") (pintype "passive"))
    )
    (net (code "74") (name "/PD5") (class "Default")
      (node (ref "R38") (pin "1") (pintype "passive"))
      (node (ref "TF_CARD") (pin "2") (pinfunction "CS/DATA3_2") (pintype "passive"))
      (node (ref "U1") (pin "160") (pinfunction "PD.5/SD0D3_160") (pintype "passive"))
    )
    (net (code "75") (name "/PD6") (class "Default")
      (node (ref "U1") (pin "161") (pinfunction "PD.6/SD0CD_161") (pintype "passive"))
    )
    (net (code "76") (name "/PD7") (class "Default")
      (node (ref "U1") (pin "162") (pinfunction "PD.7/SD0PWR_162") (pintype "passive"))
    )
    (net (code "77") (name "/PE0") (class "Default")
      (node (ref "P5") (pin "2") (pinfunction "2_2") (pintype "passive"))
      (node (ref "U1") (pin "182") (pinfunction "PE.0/UR0Tx_182") (pintype "passive"))
      (node (ref "U5") (pin "3") (pinfunction "RXD_3") (pintype "passive"))
    )
    (net (code "78") (name "/PE1") (class "Default")
      (node (ref "P5") (pin "1") (pinfunction "1_1") (pintype "passive"))
      (node (ref "U1") (pin "181") (pinfunction "PE.1/UR0Rx_181") (pintype "passive"))
      (node (ref "U5") (pin "2") (pinfunction "TXD_2") (pintype "passive"))
    )
    (net (code "79") (name "/PE2") (class "Default")
      (node (ref "IO2") (pin "24") (pinfunction "24_24") (pintype "passive"))
      (node (ref "U1") (pin "180") (pinfunction "PE.2/RMII1_MDC/SD1CMD/UR1Tx_180") (pintype "passive"))
    )
    (net (code "80") (name "/PE3") (class "Default")
      (node (ref "IO2") (pin "34") (pinfunction "34_34") (pintype "passive"))
      (node (ref "U1") (pin "179") (pinfunction "PE.3/RMII1_MDIO/SD1CLK/UR1Rx_179") (pintype "passive"))
    )
    (net (code "81") (name "/PE4") (class "Default")
      (node (ref "IO2") (pin "25") (pinfunction "25_25") (pintype "passive"))
      (node (ref "U1") (pin "178") (pinfunction "PE.4/RMII1_TxD0/SD1D0/UR1RTS_178") (pintype "passive"))
    )
    (net (code "82") (name "/PE5") (class "Default")
      (node (ref "IO2") (pin "35") (pinfunction "35_35") (pintype "passive"))
      (node (ref "U1") (pin "177") (pinfunction "PE.5/RMII1_TxD1/SD1D1/UR1CTS_177") (pintype "passive"))
    )
    (net (code "83") (name "/PE6") (class "Default")
      (node (ref "IO2") (pin "26") (pinfunction "26_26") (pintype "passive"))
      (node (ref "U1") (pin "176") (pinfunction "PE.6/RMII1_TxEn/SD1D2/UR1DTR_176") (pintype "passive"))
    )
    (net (code "84") (name "/PE7") (class "Default")
      (node (ref "IO2") (pin "36") (pinfunction "36_36") (pintype "passive"))
      (node (ref "U1") (pin "175") (pinfunction "PE.7/RMII1_RefClk/SD1D3/UR1DSR_175") (pintype "passive"))
    )
    (net (code "85") (name "/PE8") (class "Default")
      (node (ref "IO2") (pin "27") (pinfunction "27_27") (pintype "passive"))
      (node (ref "U1") (pin "174") (pinfunction "PE.8/RMII1_RxD0/SD1CD/UR1Ri_174") (pintype "passive"))
    )
    (net (code "86") (name "/PE9") (class "Default")
      (node (ref "IO2") (pin "37") (pinfunction "37_37") (pintype "passive"))
      (node (ref "U1") (pin "173") (pinfunction "PE.9/RMII1_RxD1/SD1PWR/UR1CD_173") (pintype "passive"))
    )
    (net (code "87") (name "/PE10") (class "Default")
      (node (ref "IO2") (pin "28") (pinfunction "28_28") (pintype "passive"))
      (node (ref "U1") (pin "172") (pinfunction "PE.10/RMII1_CRSDV/UR8Tx_172") (pintype "passive"))
    )
    (net (code "88") (name "/PE11") (class "Default")
      (node (ref "IO2") (pin "38") (pinfunction "38_38") (pintype "passive"))
      (node (ref "U1") (pin "171") (pinfunction "PE.11/RMII1_RxErr/UR8Rx_171") (pintype "passive"))
    )
    (net (code "89") (name "/PE12") (class "Default")
      (node (ref "IO2") (pin "29") (pinfunction "29_29") (pintype "passive"))
      (node (ref "U1") (pin "170") (pinfunction "PE.12/UR8RTS/UR3Tx_170") (pintype "passive"))
    )
    (net (code "90") (name "/PE13") (class "Default")
      (node (ref "IO2") (pin "39") (pinfunction "39_39") (pintype "passive"))
      (node (ref "U1") (pin "169") (pinfunction "PE.13/UR8CTS/UR3Rx_169") (pintype "passive"))
    )
    (net (code "91") (name "/PE14") (class "Default")
      (node (ref "IO2") (pin "31") (pinfunction "31_31") (pintype "passive"))
      (node (ref "U1") (pin "201") (pinfunction "PE.14/USB0PWREn_201") (pintype "passive"))
    )
    (net (code "92") (name "/PE15") (class "Default")
      (node (ref "IO") (pin "9") (pinfunction "9_9") (pintype "passive"))
      (node (ref "U1") (pin "200") (pinfunction "PE.15/USB1PWREn_200") (pintype "passive"))
    )
    (net (code "93") (name "/PF0") (class "Default")
      (node (ref "U1") (pin "196") (pinfunction "PF.0/RMII0_MDC_196") (pintype "passive"))
    )
    (net (code "94") (name "/PF1") (class "Default")
      (node (ref "U1") (pin "195") (pinfunction "PF.1/RMII0_MDio_195") (pintype "passive"))
    )
    (net (code "95") (name "/PF2") (class "Default")
      (node (ref "U1") (pin "194") (pinfunction "PF.2/RMII0_TxD0_194") (pintype "passive"))
    )
    (net (code "96") (name "/PF3") (class "Default")
      (node (ref "U1") (pin "193") (pinfunction "PF.3/RMII0_TxD1_193") (pintype "passive"))
    )
    (net (code "97") (name "/PF4") (class "Default")
      (node (ref "U1") (pin "192") (pinfunction "PF.4/RMII0_TxEn_192") (pintype "passive"))
    )
    (net (code "98") (name "/PF5") (class "Default")
      (node (ref "U1") (pin "191") (pinfunction "PF.5/RMII0_RefClk_191") (pintype "passive"))
    )
    (net (code "99") (name "/PF6") (class "Default")
      (node (ref "U1") (pin "190") (pinfunction "PF.6/RMII0_RxD0_190") (pintype "passive"))
    )
    (net (code "100") (name "/PF7") (class "Default")
      (node (ref "U1") (pin "189") (pinfunction "PF.7/RMII0_RxD1_189") (pintype "passive"))
    )
    (net (code "101") (name "/PF8") (class "Default")
      (node (ref "U1") (pin "188") (pinfunction "PF.8/RMII0_CRSDV_188") (pintype "passive"))
    )
    (net (code "102") (name "/PF9") (class "Default")
      (node (ref "U1") (pin "187") (pinfunction "PF.9/RMII0_RxErr_187") (pintype "passive"))
    )
    (net (code "103") (name "/PF10") (class "Default")
      (node (ref "IO2") (pin "32") (pinfunction "32_32") (pintype "passive"))
      (node (ref "U1") (pin "199") (pinfunction "PF.10/USBPWREn/WDT_nRst_199") (pintype "passive"))
    )
    (net (code "104") (name "/PF11") (class "Default")
      (node (ref "IO2") (pin "15") (pinfunction "15_15") (pintype "passive"))
      (node (ref "U1") (pin "25") (pinfunction "PF.11/UR2Tx/TM2TGL/Int0_25") (pintype "passive"))
    )
    (net (code "105") (name "/PF12") (class "Default")
      (node (ref "IO2") (pin "14") (pinfunction "14_14") (pintype "passive"))
      (node (ref "U1") (pin "24") (pinfunction "PF.12/UR2Rx/TM2CAP/Int1_24") (pintype "passive"))
    )
    (net (code "106") (name "/PF13") (class "Default")
      (node (ref "IO2") (pin "13") (pinfunction "13_13") (pintype "passive"))
      (node (ref "U1") (pin "23") (pinfunction "PF.13/UR2RTS/TM3TGL/Int2_23") (pintype "passive"))
    )
    (net (code "107") (name "/PF14") (class "Default")
      (node (ref "IO2") (pin "12") (pinfunction "12_12") (pintype "passive"))
      (node (ref "U1") (pin "22") (pinfunction "PF.14/UR2CTS/TM3CAP/Int3_22") (pintype "passive"))
    )
    (net (code "108") (name "/PG0") (class "Default")
      (node (ref "IO2") (pin "22") (pinfunction "22_22") (pintype "passive"))
      (node (ref "U1") (pin "4") (pinfunction "PG.0/IIC0SCL_4") (pintype "passive"))
    )
    (net (code "109") (name "/PG1") (class "Default")
      (node (ref "IO2") (pin "19") (pinfunction "19_19") (pintype "passive"))
      (node (ref "U1") (pin "3") (pinfunction "PG.1/IIC0SDA_3") (pintype "passive"))
    )
    (net (code "110") (name "/PG2") (class "Default")
      (node (ref "IO2") (pin "23") (pinfunction "23_23") (pintype "passive"))
      (node (ref "U1") (pin "2") (pinfunction "PG.2/IIC1SCL_2") (pintype "passive"))
    )
    (net (code "111") (name "/PG4") (class "Default")
      (node (ref "IO") (pin "2") (pinfunction "2_2") (pintype "passive"))
      (node (ref "U1") (pin "121") (pinfunction "PG.4/NCS1/UR7Tx/SPI1D2_121") (pintype "passive"))
    )
    (net (code "112") (name "/PG5") (class "Default")
      (node (ref "IO") (pin "1") (pinfunction "1_1") (pintype "passive"))
      (node (ref "U1") (pin "122") (pinfunction "PG.5/NRDY1/UR7Rx/SPI1D3_122") (pintype "passive"))
    )
    (net (code "113") (name "/PG10") (class "Default")
      (node (ref "IO2") (pin "16") (pinfunction "16_16") (pintype "passive"))
      (node (ref "U1") (pin "9") (pinfunction "PG.10/IIS_MClk/SC0_RST_9") (pintype "passive"))
    )
    (net (code "114") (name "/PG11") (class "Default")
      (node (ref "IO2") (pin "20") (pinfunction "20_20") (pintype "passive"))
      (node (ref "U1") (pin "8") (pinfunction "PG.11/IIS_DO/SC0_CLK/UR6Tx_8") (pintype "passive"))
    )
    (net (code "115") (name "/PG12") (class "Default")
      (node (ref "IO2") (pin "17") (pinfunction "17_17") (pintype "passive"))
      (node (ref "U1") (pin "7") (pinfunction "PG.12/IIS_DI/SC0_DAT/UR6Rx_7") (pintype "passive"))
    )
    (net (code "116") (name "/PG13") (class "Default")
      (node (ref "IO2") (pin "21") (pinfunction "21_21") (pintype "passive"))
      (node (ref "U1") (pin "6") (pinfunction "PG.13/IIS_BCLK/SC0PWR/UR6RTS_6") (pintype "passive"))
    )
    (net (code "117") (name "/PG14") (class "Default")
      (node (ref "IO2") (pin "18") (pinfunction "18_18") (pintype "passive"))
      (node (ref "U1") (pin "5") (pinfunction "PG.14/IIS_LRCK/SC0CD/UR6CTS_5") (pintype "passive"))
    )
    (net (code "118") (name "/PH0") (class "Default")
      (node (ref "IO") (pin "8") (pinfunction "8_8") (pintype "passive"))
      (node (ref "U1") (pin "198") (pinfunction "PH.0/USB0VbusVLD/Int0_198") (pintype "passive"))
    )
    (net (code "119") (name "/PH1") (class "Default")
      (node (ref "IO2") (pin "33") (pinfunction "33_33") (pintype "passive"))
      (node (ref "U1") (pin "197") (pinfunction "PH.1/USBOC/Int1_197") (pintype "passive"))
    )
    (net (code "120") (name "/PH2") (class "Default")
      (node (ref "IO2") (pin "30") (pinfunction "30_30") (pintype "passive"))
      (node (ref "U1") (pin "168") (pinfunction "PH.2/IIC1SCL/UR9Tx/CAN0Rx/PWM2/Int2_168") (pintype "passive"))
    )
    (net (code "121") (name "/PH3") (class "Default")
      (node (ref "IO2") (pin "40") (pinfunction "40_40") (pintype "passive"))
      (node (ref "U1") (pin "167") (pinfunction "PH.3/IIC1SDA/UR9Rx/CAN0Tx/PWM3/Int3_167") (pintype "passive"))
    )
    (net (code "122") (name "/PH4") (class "Default")
      (node (ref "IO2") (pin "10") (pinfunction "10_10") (pintype "passive"))
      (node (ref "U1") (pin "71") (pinfunction "PH.4/KPI_Row0/UR1Tx/EBI_Add0/Int4_71") (pintype "passive"))
    )
    (net (code "123") (name "/PH5") (class "Default")
      (node (ref "IO") (pin "38") (pinfunction "38_38") (pintype "passive"))
      (node (ref "U1") (pin "72") (pinfunction "PH.5/KPI_Row1/UR1Rx/EBI_Add1/Int5_72") (pintype "passive"))
    )
    (net (code "124") (name "/PH6") (class "Default")
      (node (ref "IO2") (pin "9") (pinfunction "9_9") (pintype "passive"))
      (node (ref "U1") (pin "73") (pinfunction "PH.6/KPI_Row2/SD1Cmd/UR1RTS/EBI_Add2/Int6_73") (pintype "passive"))
    )
    (net (code "125") (name "/PH7") (class "Default")
      (node (ref "IO") (pin "37") (pinfunction "37_37") (pintype "passive"))
      (node (ref "U1") (pin "74") (pinfunction "PH.7/KPI_Row3/SD1Clk/UR1CTS/EBI_Add3/Int7_74") (pintype "passive"))
    )
    (net (code "126") (name "/PH8") (class "Default")
      (node (ref "IO2") (pin "8") (pinfunction "8_8") (pintype "passive"))
      (node (ref "U1") (pin "75") (pinfunction "PH.8/KPI_Col0/SD1D0/UR4Tx/EBI_Add4_75") (pintype "passive"))
    )
    (net (code "127") (name "/PH9") (class "Default")
      (node (ref "IO") (pin "36") (pinfunction "36_36") (pintype "passive"))
      (node (ref "U1") (pin "76") (pinfunction "PH.9/KPI_Col1/SD1D1/UR4Rx/EBI_Add5_76") (pintype "passive"))
    )
    (net (code "128") (name "/PH10") (class "Default")
      (node (ref "IO2") (pin "7") (pinfunction "7_7") (pintype "passive"))
      (node (ref "U1") (pin "77") (pinfunction "PH.10/KPI_Col2/SD1D2/UR4RTS/EBI_Add6_77") (pintype "passive"))
    )
    (net (code "129") (name "/PH11") (class "Default")
      (node (ref "IO") (pin "35") (pinfunction "35_35") (pintype "passive"))
      (node (ref "U1") (pin "78") (pinfunction "PH.11/KPI_Col3/SD1D3/UR4CTS/EBI_Add7_78") (pintype "passive"))
    )
    (net (code "130") (name "/PH12") (class "Default")
      (node (ref "IO2") (pin "6") (pinfunction "6_6") (pintype "passive"))
      (node (ref "U1") (pin "79") (pinfunction "PH.12/KPI_Cl4/SD1CD/UR8Tx/SPI0CS1/EBI_Add8_79") (pintype "passive"))
    )
    (net (code "131") (name "/PH13") (class "Default")
      (node (ref "IO") (pin "34") (pinfunction "34_34") (pintype "passive"))
      (node (ref "U1") (pin "83") (pinfunction "PH.13/KPI_Col5/SD1PWR/UR8Rx/SPI1CS1/EBI_Add9_83") (pintype "passive"))
    )
    (net (code "132") (name "/PH14") (class "Default")
      (node (ref "IO") (pin "24") (pinfunction "24_24") (pintype "passive"))
      (node (ref "U1") (pin "84") (pinfunction "PH.14/KPI_Col6/UR8RTS/CAN1Rx/EBI_nBE0_84") (pintype "passive"))
    )
    (net (code "133") (name "/PH15") (class "Default")
      (node (ref "IO") (pin "33") (pinfunction "33_33") (pintype "passive"))
      (node (ref "U1") (pin "85") (pinfunction "PH.15/KPI_Col7/UR8CTS/CAN1Tx/EBI_nBE1_85") (pintype "passive"))
    )
    (net (code "134") (name "/PI0") (class "Default")
      (node (ref "IO") (pin "23") (pinfunction "23_23") (pintype "passive"))
      (node (ref "U1") (pin "86") (pinfunction "PI.0/EBI_D0_86") (pintype "passive"))
    )
    (net (code "135") (name "/PI1") (class "Default")
      (node (ref "IO") (pin "32") (pinfunction "32_32") (pintype "passive"))
      (node (ref "U1") (pin "87") (pinfunction "PI.1/NCS0/UR7Tx/EBI_D1/Int6_87") (pintype "passive"))
    )
    (net (code "136") (name "/PI2") (class "Default")
      (node (ref "IO") (pin "22") (pinfunction "22_22") (pintype "passive"))
      (node (ref "U1") (pin "88") (pinfunction "PI.2/NWP/UR7Rx/EBI_D2/Int7_88") (pintype "passive"))
    )
    (net (code "137") (name "/PI3") (class "Default")
      (node (ref "IO") (pin "31") (pinfunction "31_31") (pintype "passive"))
      (node (ref "U1") (pin "89") (pinfunction "PI.3/SClko/NALE/IIC1SCL/EBI_D3_89") (pintype "passive"))
    )
    (net (code "138") (name "/PI4") (class "Default")
      (node (ref "IO") (pin "21") (pinfunction "21_21") (pintype "passive"))
      (node (ref "U1") (pin "90") (pinfunction "PI.4/SPClk/NCLE/IIC1SDA/EBI_D4_90") (pintype "passive"))
    )
    (net (code "139") (name "/PI5") (class "Default")
      (node (ref "IO") (pin "30") (pinfunction "30_30") (pintype "passive"))
      (node (ref "U1") (pin "91") (pinfunction "PI.5/SHsync/NWE/eMMC_Cmd/EBI_D5/SD1CMD_91") (pintype "passive"))
    )
    (net (code "140") (name "/PI6") (class "Default")
      (node (ref "IO") (pin "20") (pinfunction "20_20") (pintype "passive"))
      (node (ref "U1") (pin "92") (pinfunction "PI.6/SVsync/NRE/eMMC_Clk/SC1_Rst/EBI_D6/SD1CLK_92") (pintype "passive"))
    )
    (net (code "141") (name "/PI7") (class "Default")
      (node (ref "IO") (pin "29") (pinfunction "29_29") (pintype "passive"))
      (node (ref "U1") (pin "93") (pinfunction "PI.7/SField/NRDY0/eMMC_D3/SC1_Clk/EBI_D7/SD1D0_93") (pintype "passive"))
    )
    (net (code "142") (name "/PI8") (class "Default")
      (node (ref "IO") (pin "19") (pinfunction "19_19") (pintype "passive"))
      (node (ref "U1") (pin "94") (pinfunction "PI.8/SD0/ND0/eMMC_D0/SC1_DAT/EBI_D8/SD1D1_94") (pintype "passive"))
    )
    (net (code "143") (name "/PI9") (class "Default")
      (node (ref "IO") (pin "28") (pinfunction "28_28") (pintype "passive"))
      (node (ref "U1") (pin "95") (pinfunction "PI.9/SD1/ND1/eMMC_D1/SC1_PWR/EBI_D9/SD1D2_95") (pintype "passive"))
    )
    (net (code "144") (name "/PI10") (class "Default")
      (node (ref "IO") (pin "18") (pinfunction "18_18") (pintype "passive"))
      (node (ref "U1") (pin "96") (pinfunction "PI.10/SD2/ND2/eMMC_D2/SC1_CD/EBI_D10/SD1D3_96") (pintype "passive"))
    )
    (net (code "145") (name "/PI11") (class "Default")
      (node (ref "IO") (pin "27") (pinfunction "27_27") (pintype "passive"))
      (node (ref "U1") (pin "97") (pinfunction "PI.11/SD3/ND3/SC0_Rst/EBI_D11_97") (pintype "passive"))
    )
    (net (code "146") (name "/PI12") (class "Default")
      (node (ref "IO") (pin "17") (pinfunction "17_17") (pintype "passive"))
      (node (ref "U1") (pin "98") (pinfunction "PI.12/SD4/ND4/UR8Tx/SC0_Clk/EBI_D12/SD1CD_98") (pintype "passive"))
    )
    (net (code "147") (name "/PI13") (class "Default")
      (node (ref "IO") (pin "25") (pinfunction "25_25") (pintype "passive"))
      (node (ref "U1") (pin "99") (pinfunction "PI.13/SD5/ND5/UR8Rx/SC0_DAT/EBI_D13/SD1PWR_99") (pintype "passive"))
    )
    (net (code "148") (name "/PI14") (class "Default")
      (node (ref "IO") (pin "16") (pinfunction "16_16") (pintype "passive"))
      (node (ref "U1") (pin "100") (pinfunction "PI.14/SD6/ND6/UR8RTS/SC0_PWR/EBI_D14_100") (pintype "passive"))
    )
    (net (code "149") (name "/PI15") (class "Default")
      (node (ref "IO") (pin "26") (pinfunction "26_26") (pintype "passive"))
      (node (ref "U1") (pin "101") (pinfunction "PI.15/SD7/ND7/UR8CTS/SC0_CD/EBI_D15_101") (pintype "passive"))
    )
    (net (code "150") (name "/PJ0") (class "Default")
      (node (ref "JTAG") (pin "1") (pinfunction "1_1") (pintype "passive"))
      (node (ref "U1") (pin "139") (pinfunction "PJ.0/TCK_139") (pintype "output"))
    )
    (net (code "151") (name "/PJ1") (class "Default")
      (node (ref "JTAG") (pin "2") (pinfunction "2_2") (pintype "passive"))
      (node (ref "U1") (pin "140") (pinfunction "PJ.1/TMS_140") (pintype "output"))
    )
    (net (code "152") (name "/PJ2") (class "Default")
      (node (ref "JTAG") (pin "3") (pinfunction "3_3") (pintype "passive"))
      (node (ref "U1") (pin "141") (pinfunction "PJ.2/TDI_141") (pintype "output"))
    )
    (net (code "153") (name "/PJ3") (class "Default")
      (node (ref "JTAG") (pin "4") (pinfunction "4_4") (pintype "passive"))
      (node (ref "U1") (pin "138") (pinfunction "PJ.3/TDO_138") (pintype "output"))
    )
    (net (code "154") (name "/PJ4") (class "Default")
      (node (ref "JTAG") (pin "5") (pinfunction "5_5") (pintype "passive"))
      (node (ref "U1") (pin "142") (pinfunction "PJ.4/nTRST_142") (pintype "output"))
    )
    (net (code "155") (name "/RESET") (class "Default")
      (node (ref "C5") (pin "1") (pintype "passive"))
      (node (ref "R3") (pin "2") (pintype "passive"))
      (node (ref "RESET") (pin "1") (pinfunction "1_1") (pintype "passive"))
      (node (ref "U1") (pin "143") (pinfunction "nRESET_143") (pintype "passive"))
    )
    (net (code "156") (name "/RGB_RST") (class "Default")
      (node (ref "J3") (pin "40") (pinfunction "40_40") (pintype "passive"))
    )
    (net (code "157") (name "/RGB_T_MISO") (class "Default")
      (node (ref "J3") (pin "37") (pinfunction "37_37") (pintype "passive"))
    )
    (net (code "158") (name "/RTC_VDD") (class "Default")
      (node (ref "C9") (pin "2") (pintype "passive"))
      (node (ref "D1") (pin "2") (pintype "passive"))
      (node (ref "U1") (pin "66") (pinfunction "RTC_VDD_66") (pintype "power_in"))
    )
    (net (code "159") (name "/SysPWREn") (class "Default")
      (node (ref "IO") (pin "39") (pinfunction "39_39") (pintype "passive"))
      (node (ref "U1") (pin "67") (pinfunction "SysPWREn_67") (pintype "output"))
    )
    (net (code "160") (name "/SysnWkUp") (class "Default")
      (node (ref "IO2") (pin "11") (pinfunction "11_11") (pintype "passive"))
      (node (ref "U1") (pin "68") (pinfunction "SysnWkUp_68") (pintype "input"))
    )
    (net (code "161") (name "/USB0_DM") (class "Default")
      (node (ref "R13") (pin "2") (pintype "passive"))
      (node (ref "U1") (pin "212") (pinfunction "USB0_DM_212") (pintype "passive"))
    )
    (net (code "162") (name "/USB0_DP") (class "Default")
      (node (ref "R14") (pin "2") (pintype "passive"))
      (node (ref "U1") (pin "213") (pinfunction "USB0_DP_213") (pintype "passive"))
    )
    (net (code "163") (name "/USB0_ID") (class "Default")
      (node (ref "P1") (pin "2") (pinfunction "2_2") (pintype "passive"))
      (node (ref "R17") (pin "2") (pintype "passive"))
      (node (ref "R18") (pin "2") (pintype "passive"))
      (node (ref "U1") (pin "216") (pinfunction "USB0_ID_216") (pintype "passive"))
    )
    (net (code "164") (name "/USB0_VBUS") (class "Default")
      (node (ref "R15") (pin "2") (pintype "passive"))
      (node (ref "R16") (pin "2") (pintype "passive"))
    )
    (net (code "165") (name "/USB1_DM") (class "Default")
      (node (ref "U1") (pin "206") (pinfunction "USB1_DM_206") (pintype "passive"))
    )
    (net (code "166") (name "/USB1_DP") (class "Default")
      (node (ref "U1") (pin "207") (pinfunction "USB1_DP_207") (pintype "passive"))
    )
    (net (code "167") (name "/VBAT") (class "Default")
      (node (ref "J3") (pin "1") (pinfunction "1_1") (pintype "passive"))
      (node (ref "J3") (pin "2") (pinfunction "2_2") (pintype "passive"))
    )
    (net (code "168") (name "/Vref") (class "Default")
      (node (ref "C6") (pin "1") (pintype "passive"))
      (node (ref "U1") (pin "65") (pinfunction "Vref_65") (pintype "input"))
    )
    (net (code "169") (name "/XT1_IN") (class "Default")
      (node (ref "C1") (pin "2") (pintype "passive"))
      (node (ref "R1") (pin "2") (pintype "passive"))
      (node (ref "U1") (pin "184") (pinfunction "MainXi_184") (pintype "passive"))
      (node (ref "Y1") (pin "1") (pinfunction "HOT_1") (pintype "passive"))
    )
    (net (code "170") (name "/XT1_OUT") (class "Default")
      (node (ref "C2") (pin "2") (pintype "passive"))
      (node (ref "R1") (pin "1") (pintype "passive"))
      (node (ref "U1") (pin "185") (pinfunction "MainXo_185") (pintype "passive"))
      (node (ref "Y1") (pin "3") (pinfunction "HOT_3") (pintype "passive"))
    )
    (net (code "171") (name "/XT2_IN") (class "Default")
      (node (ref "C3") (pin "2") (pintype "passive"))
      (node (ref "U1") (pin "69") (pinfunction "RTCXi_69") (pintype "passive"))
      (node (ref "Y2") (pin "1") (pinfunction "OSC1_1") (pintype "passive"))
    )
    (net (code "172") (name "/XT2_OUT") (class "Default")
      (node (ref "C4") (pin "2") (pintype "passive"))
      (node (ref "U1") (pin "70") (pinfunction "RTCXo_70") (pintype "passive"))
      (node (ref "Y2") (pin "2") (pinfunction "OSC2_2") (pintype "passive"))
    )
    (net (code "173") (name "/XTAL_U_IN") (class "Default")
      (node (ref "C68") (pin "2") (pintype "passive"))
      (node (ref "U5") (pin "8") (pinfunction "XO_8") (pintype "passive"))
      (node (ref "Y3") (pin "3") (pinfunction "HOT_3") (pintype "passive"))
    )
    (net (code "174") (name "/XTAL_U_OUT") (class "Default")
      (node (ref "C67") (pin "1") (pintype "passive"))
      (node (ref "U5") (pin "7") (pinfunction "XI_7") (pintype "passive"))
      (node (ref "Y3") (pin "1") (pinfunction "HOT_1") (pintype "passive"))
    )
    (net (code "175") (name "5V_USBIN") (class "Default")
      (node (ref "C65") (pin "1") (pintype "passive"))
      (node (ref "C66") (pin "1") (pintype "passive"))
      (node (ref "R15") (pin "1") (pintype "passive"))
      (node (ref "U5") (pin "16") (pinfunction "VCC_16") (pintype "passive"))
      (node (ref "USB") (pin "1") (pinfunction "VCC_1") (pintype "passive"))
      (node (ref "USB_DEBUG") (pin "1") (pinfunction "VCC_1") (pintype "passive"))
    )
    (net (code "176") (name "AGND") (class "Default")
      (node (ref "C58") (pin "1") (pintype "passive"))
      (node (ref "C59") (pin "1") (pintype "passive"))
      (node (ref "R2") (pin "1") (pintype "passive"))
      (node (ref "U1") (pin "58") (pinfunction "AVSS_58") (pintype "passive"))
    )
    (net (code "177") (name "AVDD") (class "Default")
      (node (ref "C58") (pin "2") (pintype "passive"))
      (node (ref "C59") (pin "2") (pintype "passive"))
      (node (ref "R4") (pin "2") (pintype "passive"))
      (node (ref "U1") (pin "59") (pinfunction "AVDD_59") (pintype "passive"))
    )
    (net (code "178") (name "GND") (class "Default")
      (node (ref "C1") (pin "1") (pintype "passive"))
      (node (ref "C10") (pin "1") (pintype "passive"))
      (node (ref "C11") (pin "1") (pintype "passive"))
      (node (ref "C12") (pin "1") (pintype "passive"))
      (node (ref "C13") (pin "1") (pintype "passive"))
      (node (ref "C14") (pin "1") (pintype "passive"))
      (node (ref "C15") (pin "1") (pintype "passive"))
      (node (ref "C16") (pin "1") (pintype "passive"))
      (node (ref "C17") (pin "1") (pintype "passive"))
      (node (ref "C18") (pin "1") (pintype "passive"))
      (node (ref "C19") (pin "1") (pintype "passive"))
      (node (ref "C2") (pin "1") (pintype "passive"))
      (node (ref "C20") (pin "1") (pintype "passive"))
      (node (ref "C21") (pin "1") (pintype "passive"))
      (node (ref "C22") (pin "1") (pintype "passive"))
      (node (ref "C23") (pin "1") (pintype "passive"))
      (node (ref "C24") (pin "1") (pintype "passive"))
      (node (ref "C25") (pin "1") (pintype "passive"))
      (node (ref "C26") (pin "1") (pintype "passive"))
      (node (ref "C27") (pin "1") (pintype "passive"))
      (node (ref "C28") (pin "1") (pintype "passive"))
      (node (ref "C29") (pin "1") (pintype "passive"))
      (node (ref "C3") (pin "1") (pintype "passive"))
      (node (ref "C30") (pin "1") (pintype "passive"))
      (node (ref "C31") (pin "1") (pintype "passive"))
      (node (ref "C32") (pin "1") (pintype "passive"))
      (node (ref "C33") (pin "1") (pintype "passive"))
      (node (ref "C34") (pin "1") (pintype "passive"))
      (node (ref "C35") (pin "1") (pintype "passive"))
      (node (ref "C36") (pin "1") (pintype "passive"))
      (node (ref "C37") (pin "1") (pintype "passive"))
      (node (ref "C38") (pin "1") (pintype "passive"))
      (node (ref "C39") (pin "1") (pintype "passive"))
      (node (ref "C4") (pin "1") (pintype "passive"))
      (node (ref "C40") (pin "1") (pintype "passive"))
      (node (ref "C41") (pin "1") (pintype "passive"))
      (node (ref "C42") (pin "1") (pintype "passive"))
      (node (ref "C5") (pin "2") (pintype "passive"))
      (node (ref "C50") (pin "1") (pintype "passive"))
      (node (ref "C51") (pin "1") (pintype "passive"))
      (node (ref "C52") (pin "1") (pintype "passive"))
      (node (ref "C53") (pin "1") (pintype "passive"))
      (node (ref "C54") (pin "1") (pintype "passive"))
      (node (ref "C55") (pin "1") (pintype "passive"))
      (node (ref "C56") (pin "1") (pintype "passive"))
      (node (ref "C57") (pin "1") (pintype "passive"))
      (node (ref "C6") (pin "2") (pintype "passive"))
      (node (ref "C60") (pin "1") (pintype "passive"))
      (node (ref "C61") (pin "1") (pintype "passive"))
      (node (ref "C62") (pin "2") (pintype "passive"))
      (node (ref "C63") (pin "2") (pintype "passive"))
      (node (ref "C64") (pin "2") (pintype "passive"))
      (node (ref "C65") (pin "2") (pintype "passive"))
      (node (ref "C66") (pin "2") (pintype "passive"))
      (node (ref "C67") (pin "2") (pintype "passive"))
      (node (ref "C68") (pin "1") (pintype "passive"))
      (node (ref "C7") (pin "1") (pintype "passive"))
      (node (ref "C8") (pin "1") (pintype "passive"))
      (node (ref "C81") (pin "2") (pintype "passive"))
      (node (ref "C9") (pin "1") (pintype "passive"))
      (node (ref "IO") (pin "40") (pinfunction "40_40") (pintype "passive"))
      (node (ref "IO") (pin "A") (pinfunction "A_A") (pintype "passive"))
      (node (ref "IO") (pin "B") (pinfunction "B_B") (pintype "passive"))
      (node (ref "IO2") (pin "1") (pinfunction "1_1") (pintype "passive"))
      (node (ref "IO2") (pin "A") (pinfunction "A_A") (pintype "passive"))
      (node (ref "IO2") (pin "B") (pinfunction "B_B") (pintype "passive"))
      (node (ref "J3") (pin "11") (pinfunction "11_11") (pintype "passive"))
      (node (ref "J3") (pin "20") (pinfunction "20_20") (pintype "passive"))
      (node (ref "J3") (pin "29") (pinfunction "29_29") (pintype "passive"))
      (node (ref "J3") (pin "A") (pinfunction "A_A") (pintype "passive"))
      (node (ref "J3") (pin "B") (pinfunction "B_B") (pintype "passive"))
      (node (ref "JTAG") (pin "6") (pinfunction "6_6") (pintype "passive"))
      (node (ref "P1") (pin "3") (pinfunction "3_3") (pintype "passive"))
      (node (ref "P5") (pin "3") (pinfunction "3_3") (pintype "passive"))
      (node (ref "R16") (pin "1") (pintype "passive"))
      (node (ref "R18") (pin "1") (pintype "passive"))
      (node (ref "R2") (pin "2") (pintype "passive"))
      (node (ref "R20") (pin "1") (pintype "passive"))
      (node (ref "R21") (pin "1") (pintype "passive"))
      (node (ref "R22") (pin "1") (pintype "passive"))
      (node (ref "R23") (pin "1") (pintype "passive"))
      (node (ref "R24") (pin "1") (pintype "passive"))
      (node (ref "R25") (pin "1") (pintype "passive"))
      (node (ref "R5") (pin "2") (pintype "passive"))
      (node (ref "R6") (pin "2") (pintype "passive"))
      (node (ref "RESET") (pin "2") (pinfunction "2_2") (pintype "passive"))
      (node (ref "TF_CARD") (pin "6") (pinfunction "VSS_6") (pintype "passive"))
      (node (ref "U1") (pin "103") (pinfunction "VSS_103") (pintype "power_in"))
      (node (ref "U1") (pin "11") (pinfunction "VSS_11") (pintype "power_in"))
      (node (ref "U1") (pin "13") (pinfunction "MVSS_13") (pintype "power_in"))
      (node (ref "U1") (pin "145") (pinfunction "VSS_145") (pintype "power_in"))
      (node (ref "U1") (pin "147") (pinfunction "MVSS_147") (pintype "power_in"))
      (node (ref "U1") (pin "149") (pinfunction "MVSS_149") (pintype "power_in"))
      (node (ref "U1") (pin "15") (pinfunction "MVSS_15") (pintype "power_in"))
      (node (ref "U1") (pin "151") (pinfunction "MVSS_151") (pintype "power_in"))
      (node (ref "U1") (pin "153") (pinfunction "VSS_153") (pintype "power_in"))
      (node (ref "U1") (pin "165") (pinfunction "PLL_VSS_165") (pintype "power_in"))
      (node (ref "U1") (pin "17") (pinfunction "MVSS_17") (pintype "power_in"))
      (node (ref "U1") (pin "186") (pinfunction "VSS_186") (pintype "power_in"))
      (node (ref "U1") (pin "19") (pinfunction "VSS_19") (pintype "power_in"))
      (node (ref "U1") (pin "202") (pinfunction "VSS_202") (pintype "power_in"))
      (node (ref "U1") (pin "205") (pinfunction "USB1_VSS_205") (pintype "power_in"))
      (node (ref "U1") (pin "211") (pinfunction "USB0_VSS_211") (pintype "passive"))
      (node (ref "U1") (pin "81") (pinfunction "VSS_81") (pintype "power_in"))
      (node (ref "U2") (pin "4") (pinfunction "GND_4") (pintype "passive"))
      (node (ref "U3") (pin "13") (pinfunction "VSS_13") (pintype "passive"))
      (node (ref "U3") (pin "36") (pinfunction "VSS_36") (pintype "passive"))
      (node (ref "U5") (pin "1") (pinfunction "GND_1") (pintype "passive"))
      (node (ref "USB") (pin "5") (pinfunction "GND_5") (pintype "passive"))
      (node (ref "USB_DEBUG") (pin "5") (pinfunction "GND_5") (pintype "passive"))
      (node (ref "Y1") (pin "2") (pinfunction "GND_2") (pintype "passive"))
      (node (ref "Y1") (pin "4") (pinfunction "GND_4") (pintype "passive"))
      (node (ref "Y3") (pin "2") (pinfunction "GND_2") (pintype "passive"))
      (node (ref "Y3") (pin "4") (pinfunction "GND_4") (pintype "passive"))
    )
    (net (code "179") (name "Net-(P1-Pad1)") (class "Default")
      (node (ref "P1") (pin "1") (pinfunction "1_1") (pintype "passive"))
      (node (ref "R19") (pin "1") (pintype "passive"))
    )
    (net (code "180") (name "Net-(P3-Pad1)") (class "Default")
      (node (ref "P3") (pin "1") (pinfunction "1_1") (pintype "passive"))
      (node (ref "R20") (pin "2") (pintype "passive"))
    )
    (net (code "181") (name "Net-(P3-Pad2)") (class "Default")
      (node (ref "P3") (pin "2") (pinfunction "2_2") (pintype "passive"))
      (node (ref "R21") (pin "2") (pintype "passive"))
    )
    (net (code "182") (name "Net-(P3-Pad3)") (class "Default")
      (node (ref "P3") (pin "3") (pinfunction "3_3") (pintype "passive"))
      (node (ref "R22") (pin "2") (pintype "passive"))
    )
    (net (code "183") (name "Net-(P3-Pad4)") (class "Default")
      (node (ref "P3") (pin "4") (pinfunction "4_4") (pintype "passive"))
      (node (ref "R23") (pin "2") (pintype "passive"))
    )
    (net (code "184") (name "Net-(U1B-USB0_Rext)") (class "Default")
      (node (ref "R6") (pin "1") (pintype "passive"))
      (node (ref "U1") (pin "215") (pinfunction "USB0_Rext_215") (pintype "passive"))
    )
    (net (code "185") (name "Net-(U1B-USB1_Rext)") (class "Default")
      (node (ref "R5") (pin "1") (pintype "passive"))
      (node (ref "U1") (pin "209") (pinfunction "USB1_Rext_209") (pintype "passive"))
    )
    (net (code "186") (name "Net-(U2-HOLD{slash}RST(IO3))") (class "Default")
      (node (ref "R12") (pin "2") (pintype "passive"))
      (node (ref "U2") (pin "7") (pinfunction "HOLD/RST(IO3)_7") (pintype "power_in"))
    )
    (net (code "187") (name "Net-(U5-D+)") (class "Default")
      (node (ref "U5") (pin "5") (pinfunction "D+_5") (pintype "passive"))
      (node (ref "USB_DEBUG") (pin "3") (pinfunction "D+_3") (pintype "passive"))
    )
    (net (code "188") (name "Net-(U5-D-)") (class "Default")
      (node (ref "U5") (pin "6") (pinfunction "D-_6") (pintype "passive"))
      (node (ref "USB_DEBUG") (pin "2") (pinfunction "D-_2") (pintype "passive"))
    )
    (net (code "189") (name "Net-(U5-V3)") (class "Default")
      (node (ref "C64") (pin "1") (pintype "passive"))
      (node (ref "U5") (pin "4") (pinfunction "V3_4") (pintype "passive"))
    )
    (net (code "190") (name "Net-(USB-D+)") (class "Default")
      (node (ref "R14") (pin "1") (pintype "passive"))
      (node (ref "USB") (pin "3") (pinfunction "D+_3") (pintype "passive"))
    )
    (net (code "191") (name "Net-(USB-D-)") (class "Default")
      (node (ref "R13") (pin "1") (pintype "passive"))
      (node (ref "USB") (pin "2") (pinfunction "D-_2") (pintype "passive"))
    )
    (net (code "192") (name "Net-(USB-NC)") (class "Default")
      (node (ref "R17") (pin "1") (pintype "passive"))
      (node (ref "USB") (pin "4") (pinfunction "NC_4") (pintype "passive"))
    )
    (net (code "193") (name "PLL_VDD12") (class "Default")
      (node (ref "C22") (pin "2") (pintype "passive"))
      (node (ref "C23") (pin "2") (pintype "passive"))
      (node (ref "C24") (pin "2") (pintype "passive"))
      (node (ref "C25") (pin "2") (pintype "passive"))
      (node (ref "C26") (pin "2") (pintype "passive"))
      (node (ref "C27") (pin "2") (pintype "passive"))
      (node (ref "C28") (pin "2") (pintype "passive"))
      (node (ref "C29") (pin "2") (pintype "passive"))
      (node (ref "C30") (pin "2") (pintype "passive"))
      (node (ref "C31") (pin "2") (pintype "passive"))
      (node (ref "C32") (pin "2") (pintype "passive"))
      (node (ref "C54") (pin "2") (pintype "passive"))
      (node (ref "C55") (pin "2") (pintype "passive"))
      (node (ref "C56") (pin "2") (pintype "passive"))
      (node (ref "C57") (pin "2") (pintype "passive"))
      (node (ref "C7") (pin "2") (pintype "passive"))
      (node (ref "C8") (pin "2") (pintype "passive"))
      (node (ref "U1") (pin "102") (pinfunction "VDD12_102") (pintype "power_in"))
      (node (ref "U1") (pin "12") (pinfunction "VDD12_12") (pintype "power_in"))
      (node (ref "U1") (pin "146") (pinfunction "VDD12_146") (pintype "power_in"))
      (node (ref "U1") (pin "163") (pinfunction "VDD12_163") (pintype "power_in"))
      (node (ref "U1") (pin "164") (pinfunction "PLL_VDD12_164") (pintype "power_in"))
      (node (ref "U1") (pin "166") (pinfunction "VDD12_166") (pintype "power_in"))
      (node (ref "U1") (pin "203") (pinfunction "VDD12_203") (pintype "power_in"))
      (node (ref "U1") (pin "204") (pinfunction "USBPLL1_VDD_204") (pintype "power_in"))
      (node (ref "U1") (pin "21") (pinfunction "VDD12_21") (pintype "power_in"))
      (node (ref "U1") (pin "210") (pinfunction "USBPLL0_VDD_210") (pintype "power_in"))
      (node (ref "U1") (pin "82") (pinfunction "VDD12_82") (pintype "power_in"))
    )
    (net (code "194") (name "UHVD33") (class "Default")
      (node (ref "C10") (pin "2") (pintype "passive"))
      (node (ref "C11") (pin "2") (pintype "passive"))
      (node (ref "C12") (pin "2") (pintype "passive"))
      (node (ref "C13") (pin "2") (pintype "passive"))
      (node (ref "C14") (pin "2") (pintype "passive"))
      (node (ref "C15") (pin "2") (pintype "passive"))
      (node (ref "C16") (pin "2") (pintype "passive"))
      (node (ref "C17") (pin "2") (pintype "passive"))
      (node (ref "C18") (pin "2") (pintype "passive"))
      (node (ref "C19") (pin "2") (pintype "passive"))
      (node (ref "C20") (pin "2") (pintype "passive"))
      (node (ref "C21") (pin "2") (pintype "passive"))
      (node (ref "C50") (pin "2") (pintype "passive"))
      (node (ref "C51") (pin "2") (pintype "passive"))
      (node (ref "C52") (pin "2") (pintype "passive"))
      (node (ref "C53") (pin "2") (pintype "passive"))
      (node (ref "C60") (pin "2") (pintype "passive"))
      (node (ref "C61") (pin "2") (pintype "passive"))
      (node (ref "C62") (pin "1") (pintype "passive"))
      (node (ref "C63") (pin "1") (pintype "passive"))
      (node (ref "C81") (pin "1") (pintype "passive"))
      (node (ref "D1") (pin "1") (pintype "passive"))
      (node (ref "R10") (pin "1") (pintype "passive"))
      (node (ref "R11") (pin "1") (pintype "passive"))
      (node (ref "R12") (pin "1") (pintype "passive"))
      (node (ref "R19") (pin "2") (pintype "passive"))
      (node (ref "R3") (pin "1") (pintype "passive"))
      (node (ref "R35") (pin "2") (pintype "passive"))
      (node (ref "R36") (pin "2") (pintype "passive"))
      (node (ref "R37") (pin "2") (pintype "passive"))
      (node (ref "R38") (pin "2") (pintype "passive"))
      (node (ref "R39") (pin "2") (pintype "passive"))
      (node (ref "R4") (pin "1") (pintype "passive"))
      (node (ref "R8") (pin "1") (pintype "passive"))
      (node (ref "R9") (pin "1") (pintype "passive"))
      (node (ref "TF_CARD") (pin "4") (pinfunction "VDD_4") (pintype "passive"))
      (node (ref "U1") (pin "10") (pinfunction "VDD33_10") (pintype "power_in"))
      (node (ref "U1") (pin "104") (pinfunction "VDD33_104") (pintype "power_in"))
      (node (ref "U1") (pin "144") (pinfunction "VDD33_144") (pintype "power_in"))
      (node (ref "U1") (pin "154") (pinfunction "VDD33_154") (pintype "power_in"))
      (node (ref "U1") (pin "183") (pinfunction "VDD33_183") (pintype "power_in"))
      (node (ref "U1") (pin "20") (pinfunction "VDD33_20") (pintype "power_in"))
      (node (ref "U1") (pin "208") (pinfunction "USB1_VDD_208") (pintype "power_in"))
      (node (ref "U1") (pin "214") (pinfunction "USB0_VDD_214") (pintype "power_in"))
      (node (ref "U1") (pin "44") (pinfunction "VDD33_44") (pintype "power_in"))
      (node (ref "U1") (pin "80") (pinfunction "VDD33_80") (pintype "power_in"))
      (node (ref "U2") (pin "8") (pinfunction "VCC_8") (pintype "passive"))
      (node (ref "U3") (pin "12") (pinfunction "VCC_12") (pintype "passive"))
      (node (ref "U3") (pin "37") (pinfunction "VCC_37") (pintype "passive"))
    )
    (net (code "195") (name "VDD18") (class "Default")
      (node (ref "C33") (pin "2") (pintype "passive"))
      (node (ref "C34") (pin "2") (pintype "passive"))
      (node (ref "C35") (pin "2") (pintype "passive"))
      (node (ref "C36") (pin "2") (pintype "passive"))
      (node (ref "C37") (pin "2") (pintype "passive"))
      (node (ref "C38") (pin "2") (pintype "passive"))
      (node (ref "C39") (pin "2") (pintype "passive"))
      (node (ref "C40") (pin "2") (pintype "passive"))
      (node (ref "C41") (pin "2") (pintype "passive"))
      (node (ref "C42") (pin "2") (pintype "passive"))
      (node (ref "U1") (pin "14") (pinfunction "MVDD_14") (pintype "power_in"))
      (node (ref "U1") (pin "148") (pinfunction "MVDD_148") (pintype "power_in"))
      (node (ref "U1") (pin "150") (pinfunction "MVDD_150") (pintype "power_in"))
      (node (ref "U1") (pin "152") (pinfunction "MVDD_152") (pintype "power_in"))
      (node (ref "U1") (pin "16") (pinfunction "MVDD_16") (pintype "power_in"))
      (node (ref "U1") (pin "18") (pinfunction "MVDD_18") (pintype "power_in"))
    )
    (net (code "196") (name "unconnected-(U5-CTS#-Pad9)") (class "Default")
      (node (ref "U5") (pin "9") (pinfunction "CTS#_9") (pintype "passive"))
    )
    (net (code "197") (name "unconnected-(U5-DCD#-Pad12)") (class "Default")
      (node (ref "U5") (pin "12") (pinfunction "DCD#_12") (pintype "passive"))
    )
    (net (code "198") (name "unconnected-(U5-DSR#-Pad10)") (class "Default")
      (node (ref "U5") (pin "10") (pinfunction "DSR#_10") (pintype "passive"))
    )
    (net (code "199") (name "unconnected-(U5-DTR#-Pad13)") (class "Default")
      (node (ref "U5") (pin "13") (pinfunction "DTR#_13") (pintype "passive"))
    )
    (net (code "200") (name "unconnected-(U5-R232-Pad15)") (class "Default")
      (node (ref "U5") (pin "15") (pinfunction "R232_15") (pintype "passive"))
    )
    (net (code "201") (name "unconnected-(U5-RI#-Pad11)") (class "Default")
      (node (ref "U5") (pin "11") (pinfunction "RI#_11") (pintype "passive"))
    )
    (net (code "202") (name "unconnected-(U5-RTS#-Pad14)") (class "Default")
      (node (ref "U5") (pin "14") (pinfunction "RTS#_14") (pintype "passive"))
    )
    (net (code "203") (name "unconnected-(USB-SHIELD-Pad6)") (class "Default")
      (node (ref "USB") (pin "6") (pinfunction "SHIELD_6") (pintype "passive"))
    )
    (net (code "204") (name "unconnected-(USB-SHIELD-Pad7)") (class "Default")
      (node (ref "USB") (pin "7") (pinfunction "SHIELD_7") (pintype "passive"))
    )
    (net (code "205") (name "unconnected-(USB-SHIELD-Pad8)") (class "Default")
      (node (ref "USB") (pin "8") (pinfunction "SHIELD_8") (pintype "passive"))
    )
    (net (code "206") (name "unconnected-(USB-SHIELD-Pad9)") (class "Default")
      (node (ref "USB") (pin "9") (pinfunction "SHIELD_9") (pintype "passive"))
    )
    (net (code "207") (name "unconnected-(USB_DEBUG-NC-Pad4)") (class "Default")
      (node (ref "USB_DEBUG") (pin "4") (pinfunction "NC_4") (pintype "passive"))
    )
    (net (code "208") (name "unconnected-(USB_DEBUG-SHIELD-Pad6)") (class "Default")
      (node (ref "USB_DEBUG") (pin "6") (pinfunction "SHIELD_6") (pintype "passive"))
    )
    (net (code "209") (name "unconnected-(USB_DEBUG-SHIELD-Pad7)") (class "Default")
      (node (ref "USB_DEBUG") (pin "7") (pinfunction "SHIELD_7") (pintype "passive"))
    )
    (net (code "210") (name "unconnected-(USB_DEBUG-SHIELD-Pad8)") (class "Default")
      (node (ref "USB_DEBUG") (pin "8") (pinfunction "SHIELD_8") (pintype "passive"))
    )
    (net (code "211") (name "unconnected-(USB_DEBUG-SHIELD-Pad9)") (class "Default")
      (node (ref "USB_DEBUG") (pin "9") (pinfunction "SHIELD_9") (pintype "passive"))
    )
  )
)
